# TestMod_SEAx.net
KiCad netlist of a schematic drawn in Altium Designer
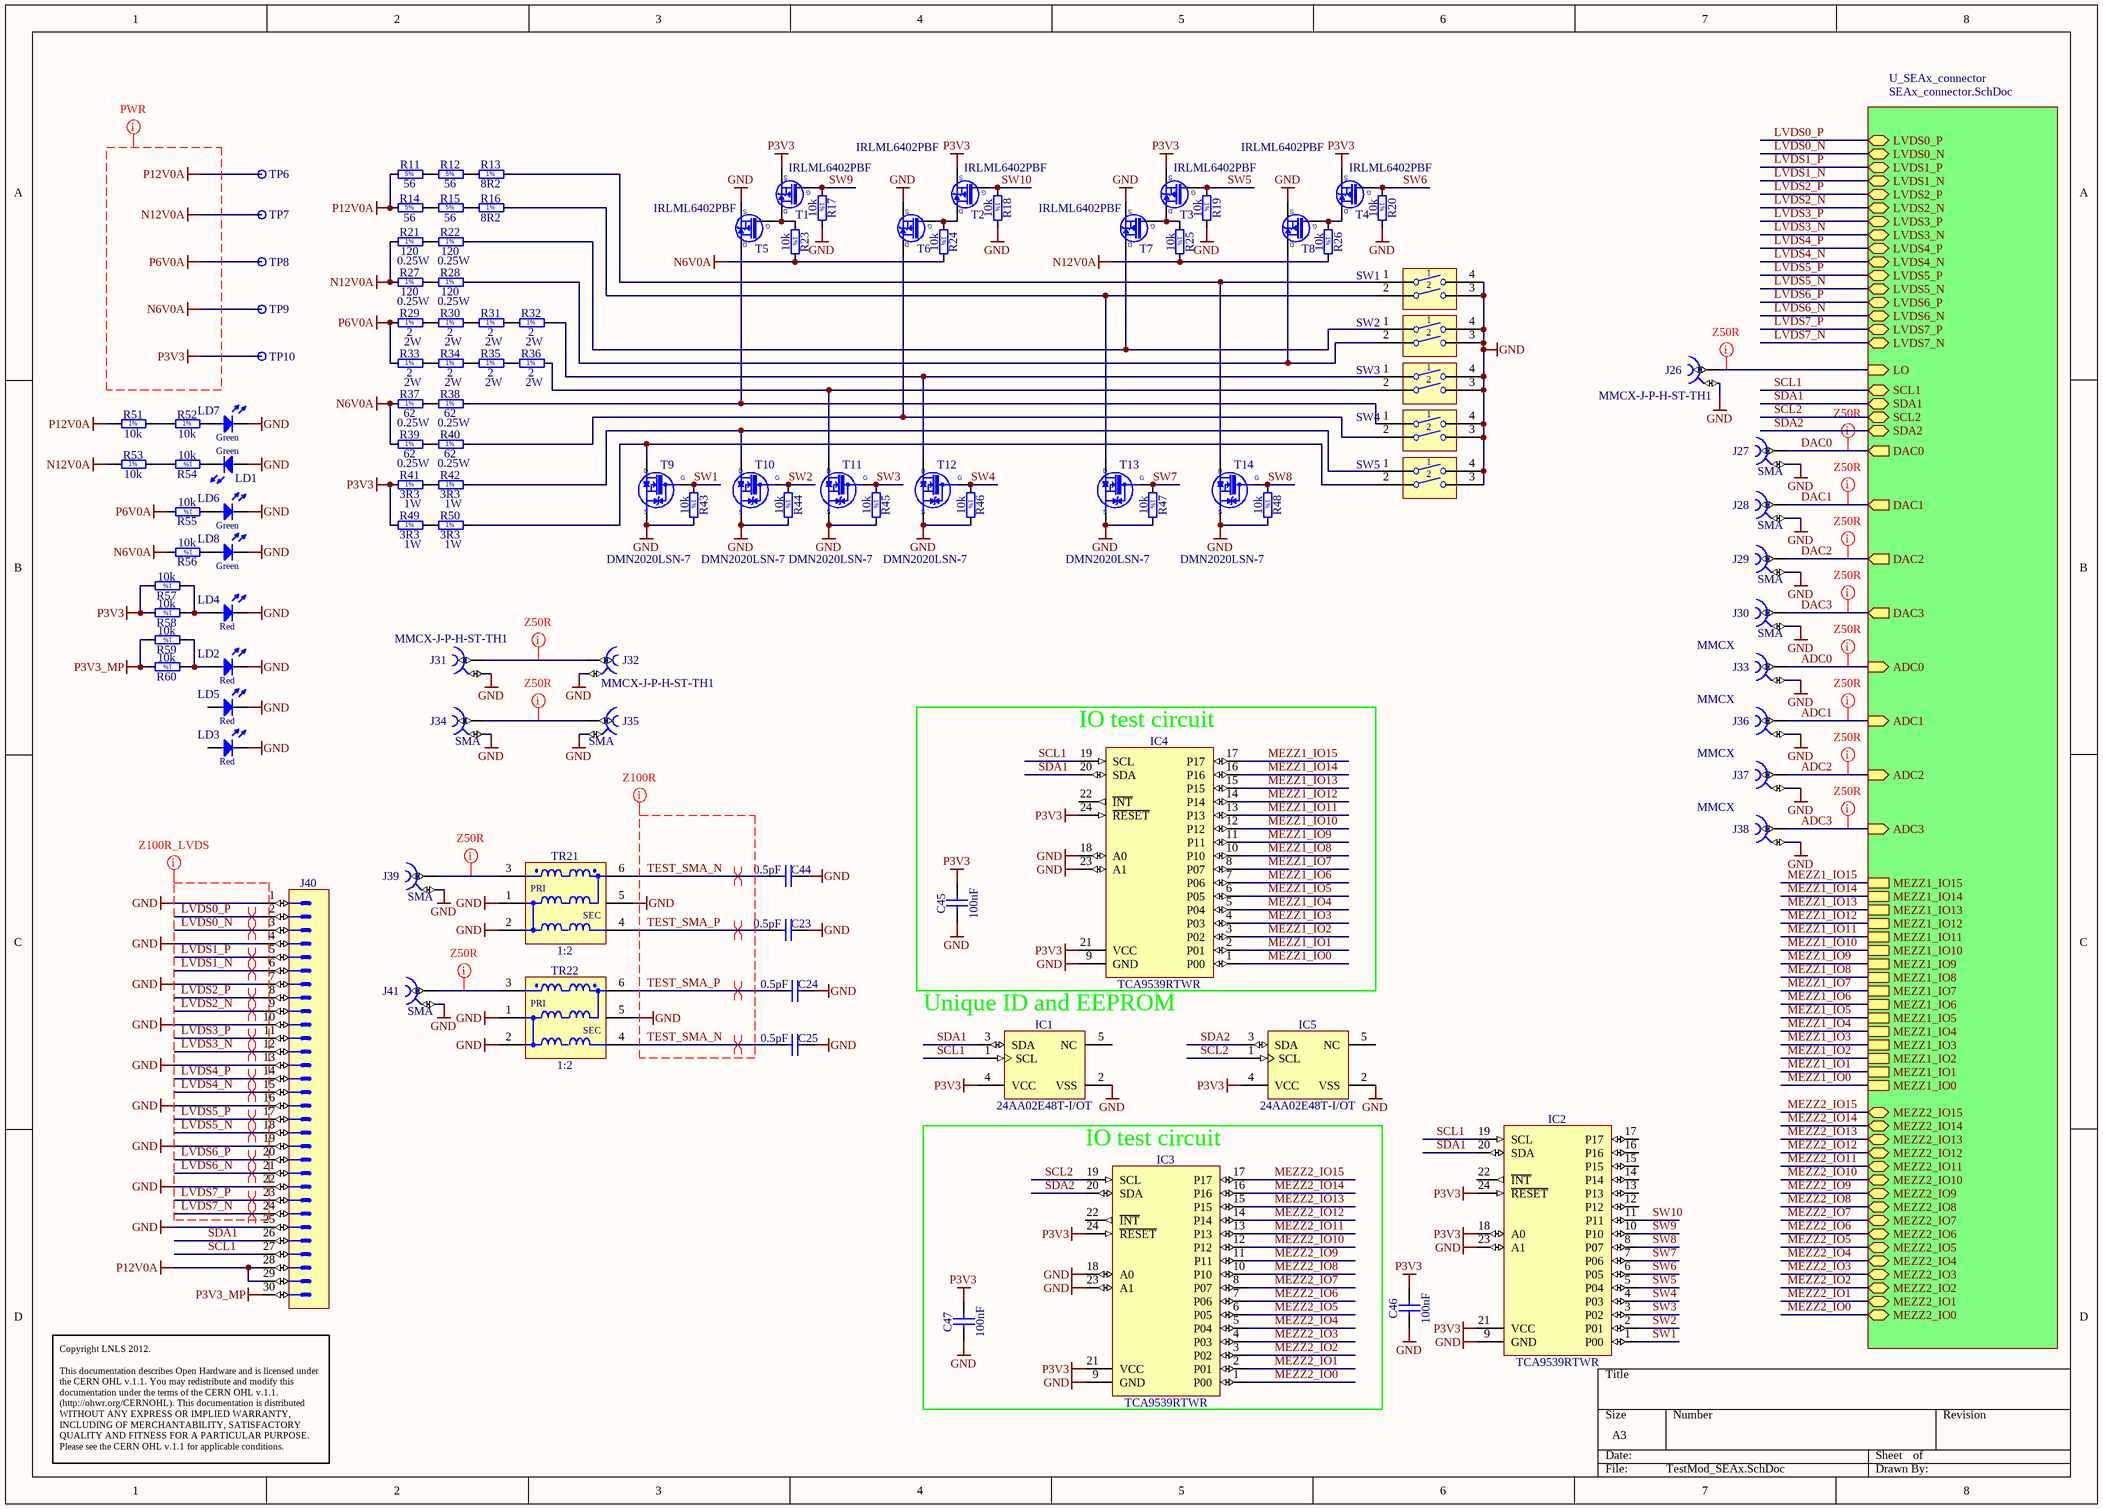
[diagram p0: TestMod_SEAx.SchDoc]

(export (version "E")
  (design (tool "Eeschema 10.0.6"))
  (components
    (comp (ref "C23")
      (value "0.5pF")
      (footprint "CAPC1005X50N")
      (description "Non-polarised capacitor")
      (fields
        (field (name "PART NUMBER") "CC0402_0.5PF_25V_0.05PF_AVX_04023J0R5ABSTR")
        (field (name "VOLTAGE") "25V")
        (field (name "AUTHOR") "CERN DEM JLC")
      )
      (libsource (lib "Capacitors") (part "Capacitor - non polarized"))
    )
    (comp (ref "C24")
      (value "0.5pF")
      (footprint "CAPC1005X50N")
      (description "Non-polarised capacitor")
      (fields
        (field (name "PART NUMBER") "CC0402_0.5PF_25V_0.05PF_AVX_04023J0R5ABSTR")
        (field (name "VOLTAGE") "25V")
        (field (name "AUTHOR") "CERN DEM JLC")
      )
      (libsource (lib "Capacitors") (part "Capacitor - non polarized"))
    )
    (comp (ref "C25")
      (value "0.5pF")
      (footprint "CAPC1005X50N")
      (description "Non-polarised capacitor")
      (fields
        (field (name "PART NUMBER") "CC0402_0.5PF_25V_0.05PF_AVX_04023J0R5ABSTR")
        (field (name "VOLTAGE") "25V")
        (field (name "AUTHOR") "CERN DEM JLC")
      )
      (libsource (lib "Capacitors") (part "Capacitor - non polarized"))
    )
    (comp (ref "C44")
      (value "0.5pF")
      (footprint "CAPC1005X50N")
      (description "Non-polarised capacitor")
      (fields
        (field (name "PART NUMBER") "CC0402_0.5PF_25V_0.05PF_AVX_04023J0R5ABSTR")
        (field (name "VOLTAGE") "25V")
        (field (name "AUTHOR") "CERN DEM JLC")
      )
      (libsource (lib "Capacitors") (part "Capacitor - non polarized"))
    )
    (comp (ref "C45")
      (value "100nF")
      (footprint "CAPC1005X55N")
      (description "Non-polarised capacitor")
      (fields
        (field (name "PART NUMBER") "CC0402_100NF_16V_10%_X5R")
        (field (name "VOLTAGE") "16V")
        (field (name "AUTHOR") "CERN DEM JLC")
      )
      (libsource (lib "Capacitors") (part "Capacitor - non polarized"))
    )
    (comp (ref "C46")
      (value "100nF")
      (footprint "CAPC1005X55N")
      (description "Non-polarised capacitor")
      (fields
        (field (name "PART NUMBER") "CC0402_100NF_16V_10%_X5R")
        (field (name "VOLTAGE") "16V")
        (field (name "AUTHOR") "CERN DEM JLC")
      )
      (libsource (lib "Capacitors") (part "Capacitor - non polarized"))
    )
    (comp (ref "C47")
      (value "100nF")
      (footprint "CAPC1005X55N")
      (description "Non-polarised capacitor")
      (fields
        (field (name "PART NUMBER") "CC0402_100NF_16V_10%_X5R")
        (field (name "VOLTAGE") "16V")
        (field (name "AUTHOR") "CERN DEM JLC")
      )
      (libsource (lib "Capacitors") (part "Capacitor - non polarized"))
    )
    (comp (ref "IC1")
      (value "24AA02E48T-I/OT")
      (footprint "SOT95P280X145-5N")
      (description "1.7V-5.5V, 2K I2C Serial EEPROM With EUI-48 Node Identity")
      (fields (field (name "MANUFACTURER") "MICROCHIP TECHNOLOGY") (field (name "AUTHOR") "CERN DEM MR"))
      (libsource (lib "ICs And Semiconductors") (part "24AA02E48T-I/OT"))
    )
    (comp (ref "IC2")
      (value "TCA9539RTWR")
      (footprint "QFN50P400X400X80-25N-S255")
      (description "Low-Voltage 16-Bit I2C and SMBus I/O Expander")
      (fields (field (name "MANUFACTURER") "TEXAS INSTRUMENTS") (field (name "AUTHOR") "CERN DEM MR"))
      (libsource (lib "ICs And Semiconductors") (part "TCA9539RTWR"))
    )
    (comp (ref "IC3")
      (value "TCA9539RTWR")
      (footprint "QFN50P400X400X80-25N-S255")
      (description "Low-Voltage 16-Bit I2C and SMBus I/O Expander")
      (fields (field (name "MANUFACTURER") "TEXAS INSTRUMENTS") (field (name "AUTHOR") "CERN DEM MR"))
      (libsource (lib "ICs And Semiconductors") (part "TCA9539RTWR"))
    )
    (comp (ref "IC4")
      (value "TCA9539RTWR")
      (footprint "QFN50P400X400X80-25N-S255")
      (description "Low-Voltage 16-Bit I2C and SMBus I/O Expander")
      (fields (field (name "MANUFACTURER") "TEXAS INSTRUMENTS") (field (name "AUTHOR") "CERN DEM MR"))
      (libsource (lib "ICs And Semiconductors") (part "TCA9539RTWR"))
    )
    (comp (ref "IC5")
      (value "24AA02E48T-I/OT")
      (footprint "SOT95P280X145-5N")
      (description "1.7V-5.5V, 2K I2C Serial EEPROM With EUI-48 Node Identity")
      (fields (field (name "MANUFACTURER") "MICROCHIP TECHNOLOGY") (field (name "AUTHOR") "CERN DEM MR"))
      (libsource (lib "ICs And Semiconductors") (part "24AA02E48T-I/OT"))
    )
    (comp (ref "J26")
      (value "Coax_1Female_1Shield")
      (footprint "SAMTEC_MMCX-J-P-H-ST-TH1")
      (fields
        (field (name "PART NUMBER") "SAMTEC_MMCX-J-P-H-ST-TH1")
        (field (name "MANUFACTURER") "SAMTEC")
        (field (name "MANUFACTURER PART NUMBER") "MMCX-J-P-H-ST-TH1")
        (field (name "AUTHOR") "CERN DEM JLC")
      )
      (libsource (lib "Connectors") (part "Coax_1Female_1Shield"))
    )
    (comp (ref "J27")
      (value "SMA")
      (footprint "AMPHENOL_901-143_IN BOARD")
      (description "AMPHENOL_901-143")
      (fields
        (field (name "MANUFACTURER") "AMPHENOL")
        (field (name "MANUFACTURER PART NUMBER") "901-143")
        (field (name "AUTHOR") "LNLS DIG GBMB")
      )
      (libsource (lib "LIBRARY_SCH") (part "CON_SMA_RA_AMP"))
    )
    (comp (ref "J28")
      (value "SMA")
      (footprint "AMPHENOL_901-143_IN BOARD")
      (description "AMPHENOL_901-143")
      (fields
        (field (name "MANUFACTURER") "AMPHENOL")
        (field (name "MANUFACTURER PART NUMBER") "901-143")
        (field (name "AUTHOR") "LNLS DIG GBMB")
      )
      (libsource (lib "LIBRARY_SCH") (part "CON_SMA_RA_AMP"))
    )
    (comp (ref "J29")
      (value "SMA")
      (footprint "AMPHENOL_901-143_IN BOARD")
      (description "AMPHENOL_901-143")
      (fields
        (field (name "MANUFACTURER") "AMPHENOL")
        (field (name "MANUFACTURER PART NUMBER") "901-143")
        (field (name "AUTHOR") "LNLS DIG GBMB")
      )
      (libsource (lib "LIBRARY_SCH") (part "CON_SMA_RA_AMP"))
    )
    (comp (ref "J30")
      (value "SMA")
      (footprint "AMPHENOL_901-143_IN BOARD")
      (description "AMPHENOL_901-143")
      (fields
        (field (name "MANUFACTURER") "AMPHENOL")
        (field (name "MANUFACTURER PART NUMBER") "901-143")
        (field (name "AUTHOR") "LNLS DIG GBMB")
      )
      (libsource (lib "LIBRARY_SCH") (part "CON_SMA_RA_AMP"))
    )
    (comp (ref "J31")
      (value "Coax_1Female_1Shield")
      (footprint "SAMTEC_MMCX-J-P-H-ST-TH1")
      (fields
        (field (name "PART NUMBER") "SAMTEC_MMCX-J-P-H-ST-TH1")
        (field (name "MANUFACTURER") "SAMTEC")
        (field (name "MANUFACTURER PART NUMBER") "MMCX-J-P-H-ST-TH1")
        (field (name "AUTHOR") "CERN DEM JLC")
      )
      (libsource (lib "Connectors") (part "Coax_1Female_1Shield"))
    )
    (comp (ref "J32")
      (value "Coax_1Female_1Shield")
      (footprint "SAMTEC_MMCX-J-P-H-ST-TH1")
      (fields
        (field (name "PART NUMBER") "SAMTEC_MMCX-J-P-H-ST-TH1")
        (field (name "MANUFACTURER") "SAMTEC")
        (field (name "MANUFACTURER PART NUMBER") "MMCX-J-P-H-ST-TH1")
        (field (name "AUTHOR") "CERN DEM JLC")
      )
      (libsource (lib "") (part "Coax_1Female_1Shield_1"))
    )
    (comp (ref "J33")
      (value "Coax_1Female_1Shield")
      (footprint "HUBER-SUHNER_85_MMCX-50-0-1/111_OE")
      (fields
        (field (name "PART NUMBER") "HUBER-SUHNER_85_MMCX-50-0-1/111_OE")
        (field (name "FAMILY") "MMCX")
        (field (name "MANUFACTURER") "HUBER+SUHNER")
        (field (name "MANUFACTURER PART NUMBER") "85_MMCX-50-0-1/111_OE")
        (field (name "AUTHOR") "CERN DEM JLC")
      )
      (libsource (lib "Connectors") (part "Coax_1Female_1Shield"))
    )
    (comp (ref "J34")
      (value "SMA")
      (footprint "TYCO_5-1814832-1")
      (fields
        (field (name "PART NUMBER") "TYCO_5-1814832-1")
        (field (name "MANUFACTURER") "TYCO ELECTRONICS")
        (field (name "MANUFACTURER PART NUMBER") "5-1814832-1")
        (field (name "AUTHOR") "CERN DEM JLC")
      )
      (libsource (lib "Connectors") (part "Coax_1Female_1Shield"))
    )
    (comp (ref "J35")
      (value "SMA")
      (footprint "TYCO_5-1814832-1")
      (fields
        (field (name "PART NUMBER") "TYCO_5-1814832-1")
        (field (name "MANUFACTURER") "TYCO ELECTRONICS")
        (field (name "MANUFACTURER PART NUMBER") "5-1814832-1")
        (field (name "AUTHOR") "CERN DEM JLC")
      )
      (libsource (lib "") (part "Coax_1Female_1Shield_1"))
    )
    (comp (ref "J36")
      (value "Coax_1Female_1Shield")
      (footprint "HUBER-SUHNER_85_MMCX-50-0-1/111_OE")
      (fields
        (field (name "PART NUMBER") "HUBER-SUHNER_85_MMCX-50-0-1/111_OE")
        (field (name "FAMILY") "MMCX")
        (field (name "MANUFACTURER") "HUBER+SUHNER")
        (field (name "MANUFACTURER PART NUMBER") "85_MMCX-50-0-1/111_OE")
        (field (name "AUTHOR") "CERN DEM JLC")
      )
      (libsource (lib "Connectors") (part "Coax_1Female_1Shield"))
    )
    (comp (ref "J37")
      (value "Coax_1Female_1Shield")
      (footprint "HUBER-SUHNER_85_MMCX-50-0-1/111_OE")
      (fields
        (field (name "PART NUMBER") "HUBER-SUHNER_85_MMCX-50-0-1/111_OE")
        (field (name "FAMILY") "MMCX")
        (field (name "MANUFACTURER") "HUBER+SUHNER")
        (field (name "MANUFACTURER PART NUMBER") "85_MMCX-50-0-1/111_OE")
        (field (name "AUTHOR") "CERN DEM JLC")
      )
      (libsource (lib "Connectors") (part "Coax_1Female_1Shield"))
    )
    (comp (ref "J38")
      (value "Coax_1Female_1Shield")
      (footprint "HUBER-SUHNER_85_MMCX-50-0-1/111_OE")
      (fields
        (field (name "PART NUMBER") "HUBER-SUHNER_85_MMCX-50-0-1/111_OE")
        (field (name "FAMILY") "MMCX")
        (field (name "MANUFACTURER") "HUBER+SUHNER")
        (field (name "MANUFACTURER PART NUMBER") "85_MMCX-50-0-1/111_OE")
        (field (name "AUTHOR") "CERN DEM JLC")
      )
      (libsource (lib "Connectors") (part "Coax_1Female_1Shield"))
    )
    (comp (ref "J39")
      (value "SMA")
      (footprint "TYCO_5-1814832-1")
      (fields
        (field (name "PART NUMBER") "TYCO_5-1814832-1")
        (field (name "MANUFACTURER") "TYCO ELECTRONICS")
        (field (name "MANUFACTURER PART NUMBER") "5-1814832-1")
        (field (name "AUTHOR") "CERN DEM JLC")
      )
      (libsource (lib "Connectors") (part "Coax_1Female_1Shield"))
    )
    (comp (ref "J40")
      (value "~")
      (footprint "3M_N2530-6002RB")
      (description "Connector 30 Male")
      (fields
        (field (name "PART NUMBER") "3M_N2530-6002RB")
        (field (name "MANUFACTURER") "3M")
        (field (name "AUTHOR") "CERN DEM JLC")
      )
      (libsource (lib "Connectors") (part "Connector 30 Male"))
    )
    (comp (ref "J41")
      (value "SMA")
      (footprint "TYCO_5-1814832-1")
      (fields
        (field (name "PART NUMBER") "TYCO_5-1814832-1")
        (field (name "MANUFACTURER") "TYCO ELECTRONICS")
        (field (name "MANUFACTURER PART NUMBER") "5-1814832-1")
        (field (name "AUTHOR") "CERN DEM JLC")
      )
      (libsource (lib "Connectors") (part "Coax_1Female_1Shield"))
    )
    (comp (ref "LD1")
      (value "Green")
      (footprint "LED_KINGBRIGHT_L-13GD")
      (description "LED Green 2mm")
      (fields
        (field (name "PART NUMBER") "LED_KINGBRIGHT_L-13GD")
        (field (name "MANUFACTURER") "KINGBRIGHT")
        (field (name "AUTHOR") "GK")
      )
      (libsource (lib "LIBRARY_SCH") (part "LED_2mm_RA_Green"))
    )
    (comp (ref "LD2")
      (value "Red")
      (footprint "LED_KINGBRIGHT_L-13ID")
      (description "LED Red 2mm")
      (fields
        (field (name "PART NUMBER") "LED_KINGBRIGHT_L-13ID")
        (field (name "MANUFACTURER") "KINGBRIGHT")
        (field (name "AUTHOR") "GK")
      )
      (libsource (lib "LIBRARY_SCH") (part "LED_2mm_RA_Red"))
    )
    (comp (ref "LD3")
      (value "Red")
      (footprint "LED_KINGBRIGHT_L-13ID")
      (description "LED Red 2mm")
      (fields
        (field (name "PART NUMBER") "LED_KINGBRIGHT_L-13ID")
        (field (name "MANUFACTURER") "KINGBRIGHT")
        (field (name "AUTHOR") "GK")
      )
      (libsource (lib "LIBRARY_SCH") (part "LED_2mm_RA_Red"))
    )
    (comp (ref "LD4")
      (value "Red")
      (footprint "LED_KINGBRIGHT_L-13ID")
      (description "LED Red 2mm")
      (fields
        (field (name "PART NUMBER") "LED_KINGBRIGHT_L-13ID")
        (field (name "MANUFACTURER") "KINGBRIGHT")
        (field (name "AUTHOR") "GK")
      )
      (libsource (lib "LIBRARY_SCH") (part "LED_2mm_RA_Red"))
    )
    (comp (ref "LD5")
      (value "Red")
      (footprint "LED_KINGBRIGHT_L-13ID")
      (description "LED Red 2mm")
      (fields
        (field (name "PART NUMBER") "LED_KINGBRIGHT_L-13ID")
        (field (name "MANUFACTURER") "KINGBRIGHT")
        (field (name "AUTHOR") "GK")
      )
      (libsource (lib "LIBRARY_SCH") (part "LED_2mm_RA_Red"))
    )
    (comp (ref "LD6")
      (value "Green")
      (footprint "LED_KINGBRIGHT_L-13GD")
      (description "LED Green 2mm")
      (fields
        (field (name "PART NUMBER") "LED_KINGBRIGHT_L-13GD")
        (field (name "MANUFACTURER") "KINGBRIGHT")
        (field (name "AUTHOR") "GK")
      )
      (libsource (lib "LIBRARY_SCH") (part "LED_2mm_RA_Green"))
    )
    (comp (ref "LD7")
      (value "Green")
      (footprint "LED_KINGBRIGHT_L-13GD")
      (description "LED Green 2mm")
      (fields
        (field (name "PART NUMBER") "LED_KINGBRIGHT_L-13GD")
        (field (name "MANUFACTURER") "KINGBRIGHT")
        (field (name "AUTHOR") "GK")
      )
      (libsource (lib "LIBRARY_SCH") (part "LED_2mm_RA_Green"))
    )
    (comp (ref "LD8")
      (value "Green")
      (footprint "LED_KINGBRIGHT_L-13GD")
      (description "LED Green 2mm")
      (fields
        (field (name "PART NUMBER") "LED_KINGBRIGHT_L-13GD")
        (field (name "MANUFACTURER") "KINGBRIGHT")
        (field (name "AUTHOR") "GK")
      )
      (libsource (lib "LIBRARY_SCH") (part "LED_2mm_RA_Green"))
    )
    (comp (ref "R11")
      (value "56")
      (footprint "RESC6331X70N")
      (description "Resistor - 5%")
      (fields
        (field (name "PART NUMBER") "R2512_56R_5%_1W_200PPM")
        (field (name "POWER") "1W")
        (field (name "AUTHOR") "CERN DEM JLC")
      )
      (libsource (lib "Resistors") (part "Resistor - 5%"))
    )
    (comp (ref "R12")
      (value "56")
      (footprint "RESC6331X70N")
      (description "Resistor - 5%")
      (fields
        (field (name "PART NUMBER") "R2512_56R_5%_1W_200PPM")
        (field (name "POWER") "1W")
        (field (name "AUTHOR") "CERN DEM JLC")
      )
      (libsource (lib "Resistors") (part "Resistor - 5%"))
    )
    (comp (ref "R13")
      (value "8R2")
      (footprint "RESC3216X65N")
      (description "Resistor - 1%")
      (fields
        (field (name "PART NUMBER") "R1206_8R2_1%_0.25W_200PPM")
        (field (name "POWER") "0.25W")
        (field (name "AUTHOR") "CERN DEM JLC")
      )
      (libsource (lib "Resistors") (part "Resistor - 1%"))
    )
    (comp (ref "R14")
      (value "56")
      (footprint "RESC6331X70N")
      (description "Resistor - 5%")
      (fields
        (field (name "PART NUMBER") "R2512_56R_5%_1W_200PPM")
        (field (name "POWER") "1W")
        (field (name "AUTHOR") "CERN DEM JLC")
      )
      (libsource (lib "Resistors") (part "Resistor - 5%"))
    )
    (comp (ref "R15")
      (value "56")
      (footprint "RESC6331X70N")
      (description "Resistor - 5%")
      (fields
        (field (name "PART NUMBER") "R2512_56R_5%_1W_200PPM")
        (field (name "POWER") "1W")
        (field (name "AUTHOR") "CERN DEM JLC")
      )
      (libsource (lib "Resistors") (part "Resistor - 5%"))
    )
    (comp (ref "R16")
      (value "8R2")
      (footprint "RESC3216X65N")
      (description "Resistor - 1%")
      (fields
        (field (name "PART NUMBER") "R1206_8R2_1%_0.25W_200PPM")
        (field (name "POWER") "0.25W")
        (field (name "AUTHOR") "CERN DEM JLC")
      )
      (libsource (lib "Resistors") (part "Resistor - 1%"))
    )
    (comp (ref "R17")
      (value "10k")
      (footprint "RESC1005X40N")
      (description "Resistor - 1%")
      (fields
        (field (name "PART NUMBER") "R0402_10K_1%_0.0625W_100PPM")
        (field (name "POWER") "0.0625W")
        (field (name "AUTHOR") "CERN DEM JLC")
      )
      (libsource (lib "Resistors") (part "Resistor - 1%"))
    )
    (comp (ref "R18")
      (value "10k")
      (footprint "RESC1005X40N")
      (description "Resistor - 1%")
      (fields
        (field (name "PART NUMBER") "R0402_10K_1%_0.0625W_100PPM")
        (field (name "POWER") "0.0625W")
        (field (name "AUTHOR") "CERN DEM JLC")
      )
      (libsource (lib "Resistors") (part "Resistor - 1%"))
    )
    (comp (ref "R19")
      (value "10k")
      (footprint "RESC1005X40N")
      (description "Resistor - 1%")
      (fields
        (field (name "PART NUMBER") "R0402_10K_1%_0.0625W_100PPM")
        (field (name "POWER") "0.0625W")
        (field (name "AUTHOR") "CERN DEM JLC")
      )
      (libsource (lib "Resistors") (part "Resistor - 1%"))
    )
    (comp (ref "R20")
      (value "10k")
      (footprint "RESC1005X40N")
      (description "Resistor - 1%")
      (fields
        (field (name "PART NUMBER") "R0402_10K_1%_0.0625W_100PPM")
        (field (name "POWER") "0.0625W")
        (field (name "AUTHOR") "CERN DEM JLC")
      )
      (libsource (lib "Resistors") (part "Resistor - 1%"))
    )
    (comp (ref "R21")
      (value "120")
      (footprint "RESC3216X65N")
      (description "Resistor - 1%")
      (fields
        (field (name "PART NUMBER") "R1206_120R_1%_0.25W_100PPM")
        (field (name "POWER") "0.25W")
        (field (name "TOLERANCE") "±1%")
        (field (name "AUTHOR") "CERN DEM JLC")
      )
      (libsource (lib "Resistors") (part "Resistor - 1%"))
    )
    (comp (ref "R22")
      (value "120")
      (footprint "RESC3216X65N")
      (description "Resistor - 1%")
      (fields
        (field (name "PART NUMBER") "R1206_120R_1%_0.25W_100PPM")
        (field (name "POWER") "0.25W")
        (field (name "TOLERANCE") "±1%")
        (field (name "AUTHOR") "CERN DEM JLC")
      )
      (libsource (lib "Resistors") (part "Resistor - 1%"))
    )
    (comp (ref "R23")
      (value "10k")
      (footprint "RESC1005X40N")
      (description "Resistor - 1%")
      (fields
        (field (name "PART NUMBER") "R0402_10K_1%_0.0625W_100PPM")
        (field (name "POWER") "0.0625W")
        (field (name "AUTHOR") "CERN DEM JLC")
      )
      (libsource (lib "Resistors") (part "Resistor - 1%"))
    )
    (comp (ref "R24")
      (value "10k")
      (footprint "RESC1005X40N")
      (description "Resistor - 1%")
      (fields
        (field (name "PART NUMBER") "R0402_10K_1%_0.0625W_100PPM")
        (field (name "POWER") "0.0625W")
        (field (name "AUTHOR") "CERN DEM JLC")
      )
      (libsource (lib "Resistors") (part "Resistor - 1%"))
    )
    (comp (ref "R25")
      (value "10k")
      (footprint "RESC1005X40N")
      (description "Resistor - 1%")
      (fields
        (field (name "PART NUMBER") "R0402_10K_1%_0.0625W_100PPM")
        (field (name "POWER") "0.0625W")
        (field (name "AUTHOR") "CERN DEM JLC")
      )
      (libsource (lib "Resistors") (part "Resistor - 1%"))
    )
    (comp (ref "R26")
      (value "10k")
      (footprint "RESC1005X40N")
      (description "Resistor - 1%")
      (fields
        (field (name "PART NUMBER") "R0402_10K_1%_0.0625W_100PPM")
        (field (name "POWER") "0.0625W")
        (field (name "AUTHOR") "CERN DEM JLC")
      )
      (libsource (lib "Resistors") (part "Resistor - 1%"))
    )
    (comp (ref "R27")
      (value "120")
      (footprint "RESC3216X65N")
      (description "Resistor - 1%")
      (fields
        (field (name "PART NUMBER") "R1206_120R_1%_0.25W_100PPM")
        (field (name "POWER") "0.25W")
        (field (name "TOLERANCE") "±1%")
        (field (name "AUTHOR") "CERN DEM JLC")
      )
      (libsource (lib "Resistors") (part "Resistor - 1%"))
    )
    (comp (ref "R28")
      (value "120")
      (footprint "RESC3216X65N")
      (description "Resistor - 1%")
      (fields
        (field (name "PART NUMBER") "R1206_120R_1%_0.25W_100PPM")
        (field (name "POWER") "0.25W")
        (field (name "TOLERANCE") "±1%")
        (field (name "AUTHOR") "CERN DEM JLC")
      )
      (libsource (lib "Resistors") (part "Resistor - 1%"))
    )
    (comp (ref "R29")
      (value "2")
      (footprint "RESM11670X449N")
      (description "Resistor - 1%")
      (fields
        (field (name "PART NUMBER") "R4527_2R_1%_2W_50PPM")
        (field (name "POWER") "2W")
        (field (name "TOLERANCE") "±1%")
        (field (name "AUTHOR") "CERN DEM JLC")
      )
      (libsource (lib "Resistors") (part "Resistor - 1%"))
    )
    (comp (ref "R30")
      (value "2")
      (footprint "RESM11670X449N")
      (description "Resistor - 1%")
      (fields
        (field (name "PART NUMBER") "R4527_2R_1%_2W_50PPM")
        (field (name "POWER") "2W")
        (field (name "TOLERANCE") "±1%")
        (field (name "AUTHOR") "CERN DEM JLC")
      )
      (libsource (lib "Resistors") (part "Resistor - 1%"))
    )
    (comp (ref "R31")
      (value "2")
      (footprint "RESM11670X449N")
      (description "Resistor - 1%")
      (fields
        (field (name "PART NUMBER") "R4527_2R_1%_2W_50PPM")
        (field (name "POWER") "2W")
        (field (name "TOLERANCE") "±1%")
        (field (name "AUTHOR") "CERN DEM JLC")
      )
      (libsource (lib "Resistors") (part "Resistor - 1%"))
    )
    (comp (ref "R32")
      (value "2")
      (footprint "RESM11670X449N")
      (description "Resistor - 1%")
      (fields
        (field (name "PART NUMBER") "R4527_2R_1%_2W_50PPM")
        (field (name "POWER") "2W")
        (field (name "TOLERANCE") "±1%")
        (field (name "AUTHOR") "CERN DEM JLC")
      )
      (libsource (lib "Resistors") (part "Resistor - 1%"))
    )
    (comp (ref "R33")
      (value "2")
      (footprint "RESM11670X449N")
      (description "Resistor - 1%")
      (fields
        (field (name "PART NUMBER") "R4527_2R_1%_2W_50PPM")
        (field (name "POWER") "2W")
        (field (name "TOLERANCE") "±1%")
        (field (name "AUTHOR") "CERN DEM JLC")
      )
      (libsource (lib "Resistors") (part "Resistor - 1%"))
    )
    (comp (ref "R34")
      (value "2")
      (footprint "RESM11670X449N")
      (description "Resistor - 1%")
      (fields
        (field (name "PART NUMBER") "R4527_2R_1%_2W_50PPM")
        (field (name "POWER") "2W")
        (field (name "TOLERANCE") "±1%")
        (field (name "AUTHOR") "CERN DEM JLC")
      )
      (libsource (lib "Resistors") (part "Resistor - 1%"))
    )
    (comp (ref "R35")
      (value "2")
      (footprint "RESM11670X449N")
      (description "Resistor - 1%")
      (fields
        (field (name "PART NUMBER") "R4527_2R_1%_2W_50PPM")
        (field (name "POWER") "2W")
        (field (name "TOLERANCE") "±1%")
        (field (name "AUTHOR") "CERN DEM JLC")
      )
      (libsource (lib "Resistors") (part "Resistor - 1%"))
    )
    (comp (ref "R36")
      (value "2")
      (footprint "RESM11670X449N")
      (description "Resistor - 1%")
      (fields
        (field (name "PART NUMBER") "R4527_2R_1%_2W_50PPM")
        (field (name "POWER") "2W")
        (field (name "TOLERANCE") "±1%")
        (field (name "AUTHOR") "CERN DEM JLC")
      )
      (libsource (lib "Resistors") (part "Resistor - 1%"))
    )
    (comp (ref "R37")
      (value "62")
      (footprint "RESC3216X65N")
      (description "Resistor - 1%")
      (fields
        (field (name "PART NUMBER") "R1206_62R_1%_0.25W_100PPM")
        (field (name "POWER") "0.25W")
        (field (name "TOLERANCE") "±1%")
        (field (name "AUTHOR") "CERN DEM JLC")
      )
      (libsource (lib "Resistors") (part "Resistor - 1%"))
    )
    (comp (ref "R38")
      (value "62")
      (footprint "RESC3216X65N")
      (description "Resistor - 1%")
      (fields
        (field (name "PART NUMBER") "R1206_62R_1%_0.25W_100PPM")
        (field (name "POWER") "0.25W")
        (field (name "TOLERANCE") "±1%")
        (field (name "AUTHOR") "CERN DEM JLC")
      )
      (libsource (lib "Resistors") (part "Resistor - 1%"))
    )
    (comp (ref "R39")
      (value "62")
      (footprint "RESC3216X65N")
      (description "Resistor - 1%")
      (fields
        (field (name "PART NUMBER") "R1206_62R_1%_0.25W_100PPM")
        (field (name "POWER") "0.25W")
        (field (name "TOLERANCE") "±1%")
        (field (name "AUTHOR") "CERN DEM JLC")
      )
      (libsource (lib "Resistors") (part "Resistor - 1%"))
    )
    (comp (ref "R40")
      (value "62")
      (footprint "RESC3216X65N")
      (description "Resistor - 1%")
      (fields
        (field (name "PART NUMBER") "R1206_62R_1%_0.25W_100PPM")
        (field (name "POWER") "0.25W")
        (field (name "TOLERANCE") "±1%")
        (field (name "AUTHOR") "CERN DEM JLC")
      )
      (libsource (lib "Resistors") (part "Resistor - 1%"))
    )
    (comp (ref "R41")
      (value "3R3")
      (footprint "RESC6331X70N")
      (description "Resistor - 1%")
      (fields
        (field (name "PART NUMBER") "R2512_3R3_1%_1W_200PPM")
        (field (name "POWER") "1W")
        (field (name "TOLERANCE") "±1%")
        (field (name "AUTHOR") "CERN DEM JLC")
      )
      (libsource (lib "Resistors") (part "Resistor - 1%"))
    )
    (comp (ref "R42")
      (value "3R3")
      (footprint "RESC6331X70N")
      (description "Resistor - 1%")
      (fields
        (field (name "PART NUMBER") "R2512_3R3_1%_1W_200PPM")
        (field (name "POWER") "1W")
        (field (name "TOLERANCE") "±1%")
        (field (name "AUTHOR") "CERN DEM JLC")
      )
      (libsource (lib "Resistors") (part "Resistor - 1%"))
    )
    (comp (ref "R43")
      (value "10k")
      (footprint "RESC1005X40N")
      (description "Resistor - 1%")
      (fields
        (field (name "PART NUMBER") "R0402_10K_1%_0.0625W_100PPM")
        (field (name "POWER") "0.0625W")
        (field (name "AUTHOR") "CERN DEM JLC")
      )
      (libsource (lib "Resistors") (part "Resistor - 1%"))
    )
    (comp (ref "R44")
      (value "10k")
      (footprint "RESC1005X40N")
      (description "Resistor - 1%")
      (fields
        (field (name "PART NUMBER") "R0402_10K_1%_0.0625W_100PPM")
        (field (name "POWER") "0.0625W")
        (field (name "AUTHOR") "CERN DEM JLC")
      )
      (libsource (lib "Resistors") (part "Resistor - 1%"))
    )
    (comp (ref "R45")
      (value "10k")
      (footprint "RESC1005X40N")
      (description "Resistor - 1%")
      (fields
        (field (name "PART NUMBER") "R0402_10K_1%_0.0625W_100PPM")
        (field (name "POWER") "0.0625W")
        (field (name "AUTHOR") "CERN DEM JLC")
      )
      (libsource (lib "Resistors") (part "Resistor - 1%"))
    )
    (comp (ref "R46")
      (value "10k")
      (footprint "RESC1005X40N")
      (description "Resistor - 1%")
      (fields
        (field (name "PART NUMBER") "R0402_10K_1%_0.0625W_100PPM")
        (field (name "POWER") "0.0625W")
        (field (name "AUTHOR") "CERN DEM JLC")
      )
      (libsource (lib "Resistors") (part "Resistor - 1%"))
    )
    (comp (ref "R47")
      (value "10k")
      (footprint "RESC1005X40N")
      (description "Resistor - 1%")
      (fields
        (field (name "PART NUMBER") "R0402_10K_1%_0.0625W_100PPM")
        (field (name "POWER") "0.0625W")
        (field (name "AUTHOR") "CERN DEM JLC")
      )
      (libsource (lib "Resistors") (part "Resistor - 1%"))
    )
    (comp (ref "R48")
      (value "10k")
      (footprint "RESC1005X40N")
      (description "Resistor - 1%")
      (fields
        (field (name "PART NUMBER") "R0402_10K_1%_0.0625W_100PPM")
        (field (name "POWER") "0.0625W")
        (field (name "AUTHOR") "CERN DEM JLC")
      )
      (libsource (lib "Resistors") (part "Resistor - 1%"))
    )
    (comp (ref "R49")
      (value "3R3")
      (footprint "RESC6331X70N")
      (description "Resistor - 1%")
      (fields
        (field (name "PART NUMBER") "R2512_3R3_1%_1W_200PPM")
        (field (name "POWER") "1W")
        (field (name "TOLERANCE") "±1%")
        (field (name "AUTHOR") "CERN DEM JLC")
      )
      (libsource (lib "Resistors") (part "Resistor - 1%"))
    )
    (comp (ref "R50")
      (value "3R3")
      (footprint "RESC6331X70N")
      (description "Resistor - 1%")
      (fields
        (field (name "PART NUMBER") "R2512_3R3_1%_1W_200PPM")
        (field (name "POWER") "1W")
        (field (name "TOLERANCE") "±1%")
        (field (name "AUTHOR") "CERN DEM JLC")
      )
      (libsource (lib "Resistors") (part "Resistor - 1%"))
    )
    (comp (ref "R51")
      (value "10k")
      (footprint "RESC1005X40N")
      (description "Resistor - 1%")
      (fields
        (field (name "PART NUMBER") "R0402_10K_1%_0.0625W_100PPM")
        (field (name "POWER") "0.0625W")
        (field (name "AUTHOR") "CERN DEM JLC")
      )
      (libsource (lib "Resistors") (part "Resistor - 1%"))
    )
    (comp (ref "R52")
      (value "10k")
      (footprint "RESC1005X40N")
      (description "Resistor - 1%")
      (fields
        (field (name "PART NUMBER") "R0402_10K_1%_0.0625W_100PPM")
        (field (name "POWER") "0.0625W")
        (field (name "AUTHOR") "CERN DEM JLC")
      )
      (libsource (lib "Resistors") (part "Resistor - 1%"))
    )
    (comp (ref "R53")
      (value "10k")
      (footprint "RESC1005X40N")
      (description "Resistor - 1%")
      (fields
        (field (name "PART NUMBER") "R0402_10K_1%_0.0625W_100PPM")
        (field (name "POWER") "0.0625W")
        (field (name "AUTHOR") "CERN DEM JLC")
      )
      (libsource (lib "Resistors") (part "Resistor - 1%"))
    )
    (comp (ref "R54")
      (value "10k")
      (footprint "RESC1005X40N")
      (description "Resistor - 1%")
      (fields
        (field (name "PART NUMBER") "R0402_10K_1%_0.0625W_100PPM")
        (field (name "POWER") "0.0625W")
        (field (name "AUTHOR") "CERN DEM JLC")
      )
      (libsource (lib "Resistors") (part "Resistor - 1%"))
    )
    (comp (ref "R55")
      (value "10k")
      (footprint "RESC1005X40N")
      (description "Resistor - 1%")
      (fields
        (field (name "PART NUMBER") "R0402_10K_1%_0.0625W_100PPM")
        (field (name "POWER") "0.0625W")
        (field (name "AUTHOR") "CERN DEM JLC")
      )
      (libsource (lib "Resistors") (part "Resistor - 1%"))
    )
    (comp (ref "R56")
      (value "10k")
      (footprint "RESC1005X40N")
      (description "Resistor - 1%")
      (fields
        (field (name "PART NUMBER") "R0402_10K_1%_0.0625W_100PPM")
        (field (name "POWER") "0.0625W")
        (field (name "AUTHOR") "CERN DEM JLC")
      )
      (libsource (lib "Resistors") (part "Resistor - 1%"))
    )
    (comp (ref "R57")
      (value "10k")
      (footprint "RESC1005X40N")
      (description "Resistor - 1%")
      (fields
        (field (name "PART NUMBER") "R0402_10K_1%_0.0625W_100PPM")
        (field (name "POWER") "0.0625W")
        (field (name "AUTHOR") "CERN DEM JLC")
      )
      (libsource (lib "Resistors") (part "Resistor - 1%"))
    )
    (comp (ref "R58")
      (value "10k")
      (footprint "RESC1005X40N")
      (description "Resistor - 1%")
      (fields
        (field (name "PART NUMBER") "R0402_10K_1%_0.0625W_100PPM")
        (field (name "POWER") "0.0625W")
        (field (name "AUTHOR") "CERN DEM JLC")
      )
      (libsource (lib "Resistors") (part "Resistor - 1%"))
    )
    (comp (ref "R59")
      (value "10k")
      (footprint "RESC1005X40N")
      (description "Resistor - 1%")
      (fields
        (field (name "PART NUMBER") "R0402_10K_1%_0.0625W_100PPM")
        (field (name "POWER") "0.0625W")
        (field (name "AUTHOR") "CERN DEM JLC")
      )
      (libsource (lib "Resistors") (part "Resistor - 1%"))
    )
    (comp (ref "R60")
      (value "10k")
      (footprint "RESC1005X40N")
      (description "Resistor - 1%")
      (fields
        (field (name "PART NUMBER") "R0402_10K_1%_0.0625W_100PPM")
        (field (name "POWER") "0.0625W")
        (field (name "AUTHOR") "CERN DEM JLC")
      )
      (libsource (lib "Resistors") (part "Resistor - 1%"))
    )
    (comp (ref "SW1")
      (value "Switch")
      (footprint "SW_OMRON_A6S-2102-H")
      (description "2 Ways SPST DIP Switch")
      (fields
        (field (name "PART NUMBER") "SW_OMRON_A6S-2102-H")
        (field (name "MANUFACTURER") "OMRON")
        (field (name "AUTHOR") "CERN DEM JMW")
      )
      (libsource (lib "Eletro-mechanical") (part "SW 2x SPST DIP Switch"))
    )
    (comp (ref "SW2")
      (value "Switch")
      (footprint "SW_OMRON_A6S-2102-H")
      (description "2 Ways SPST DIP Switch")
      (fields
        (field (name "PART NUMBER") "SW_OMRON_A6S-2102-H")
        (field (name "MANUFACTURER") "OMRON")
        (field (name "AUTHOR") "CERN DEM JMW")
      )
      (libsource (lib "Eletro-mechanical") (part "SW 2x SPST DIP Switch"))
    )
    (comp (ref "SW3")
      (value "Switch")
      (footprint "SW_OMRON_A6S-2102-H")
      (description "2 Ways SPST DIP Switch")
      (fields
        (field (name "PART NUMBER") "SW_OMRON_A6S-2102-H")
        (field (name "MANUFACTURER") "OMRON")
        (field (name "AUTHOR") "CERN DEM JMW")
      )
      (libsource (lib "Eletro-mechanical") (part "SW 2x SPST DIP Switch"))
    )
    (comp (ref "SW4")
      (value "Switch")
      (footprint "SW_OMRON_A6S-2102-H")
      (description "2 Ways SPST DIP Switch")
      (fields
        (field (name "PART NUMBER") "SW_OMRON_A6S-2102-H")
        (field (name "MANUFACTURER") "OMRON")
        (field (name "AUTHOR") "CERN DEM JMW")
      )
      (libsource (lib "Eletro-mechanical") (part "SW 2x SPST DIP Switch"))
    )
    (comp (ref "SW5")
      (value "Switch")
      (footprint "SW_OMRON_A6S-2102-H")
      (description "2 Ways SPST DIP Switch")
      (fields
        (field (name "PART NUMBER") "SW_OMRON_A6S-2102-H")
        (field (name "MANUFACTURER") "OMRON")
        (field (name "AUTHOR") "CERN DEM JMW")
      )
      (libsource (lib "Eletro-mechanical") (part "SW 2x SPST DIP Switch"))
    )
    (comp (ref "T1")
      (value "IRLML6402PBF")
      (footprint "SOT95P237X112-3N")
      (description "P-CHANNEL MOSFET WITH ZENER DIODE")
      (fields (field (name "MANUFACTURER") "INTERNATIONAL RECTIFIER") (field (name "AUTHOR") "CERN DEM JLC"))
      (libsource (lib "ICs And Semiconductors") (part "P-MOSFET-DZ 1G 2S 3D"))
    )
    (comp (ref "T2")
      (value "IRLML6402PBF")
      (footprint "SOT95P237X112-3N")
      (description "P-CHANNEL MOSFET WITH ZENER DIODE")
      (fields (field (name "MANUFACTURER") "INTERNATIONAL RECTIFIER") (field (name "AUTHOR") "CERN DEM JLC"))
      (libsource (lib "ICs And Semiconductors") (part "P-MOSFET-DZ 1G 2S 3D"))
    )
    (comp (ref "T3")
      (value "IRLML6402PBF")
      (footprint "SOT95P237X112-3N")
      (description "P-CHANNEL MOSFET WITH ZENER DIODE")
      (fields (field (name "MANUFACTURER") "INTERNATIONAL RECTIFIER") (field (name "AUTHOR") "CERN DEM JLC"))
      (libsource (lib "ICs And Semiconductors") (part "P-MOSFET-DZ 1G 2S 3D"))
    )
    (comp (ref "T4")
      (value "IRLML6402PBF")
      (footprint "SOT95P237X112-3N")
      (description "P-CHANNEL MOSFET WITH ZENER DIODE")
      (fields (field (name "MANUFACTURER") "INTERNATIONAL RECTIFIER") (field (name "AUTHOR") "CERN DEM JLC"))
      (libsource (lib "ICs And Semiconductors") (part "P-MOSFET-DZ 1G 2S 3D"))
    )
    (comp (ref "T5")
      (value "IRLML6402PBF")
      (footprint "SOT95P237X112-3N")
      (description "P-CHANNEL MOSFET WITH ZENER DIODE")
      (fields (field (name "MANUFACTURER") "INTERNATIONAL RECTIFIER") (field (name "AUTHOR") "CERN DEM JLC"))
      (libsource (lib "ICs And Semiconductors") (part "P-MOSFET-DZ 1G 2S 3D"))
    )
    (comp (ref "T6")
      (value "IRLML6402PBF")
      (footprint "SOT95P237X112-3N")
      (description "P-CHANNEL MOSFET WITH ZENER DIODE")
      (fields (field (name "MANUFACTURER") "INTERNATIONAL RECTIFIER") (field (name "AUTHOR") "CERN DEM JLC"))
      (libsource (lib "ICs And Semiconductors") (part "P-MOSFET-DZ 1G 2S 3D"))
    )
    (comp (ref "T7")
      (value "IRLML6402PBF")
      (footprint "SOT95P237X112-3N")
      (description "P-CHANNEL MOSFET WITH ZENER DIODE")
      (fields (field (name "MANUFACTURER") "INTERNATIONAL RECTIFIER") (field (name "AUTHOR") "CERN DEM JLC"))
      (libsource (lib "ICs And Semiconductors") (part "P-MOSFET-DZ 1G 2S 3D"))
    )
    (comp (ref "T8")
      (value "IRLML6402PBF")
      (footprint "SOT95P237X112-3N")
      (description "P-CHANNEL MOSFET WITH ZENER DIODE")
      (fields (field (name "MANUFACTURER") "INTERNATIONAL RECTIFIER") (field (name "AUTHOR") "CERN DEM JLC"))
      (libsource (lib "ICs And Semiconductors") (part "P-MOSFET-DZ 1G 2S 3D"))
    )
    (comp (ref "T9")
      (value "DMN2020LSN-7")
      (footprint "SOT95P285X140-3N")
      (description "20V, 6.9A, N-Channel Enhancement Mode MOSFET")
      (fields (field (name "MANUFACTURER") "DIODES INCORPORATED") (field (name "AUTHOR") "CERN DEM JLC"))
      (libsource (lib "ICs And Semiconductors") (part "DMN2020LSN-7"))
    )
    (comp (ref "T10")
      (value "DMN2020LSN-7")
      (footprint "SOT95P285X140-3N")
      (description "20V, 6.9A, N-Channel Enhancement Mode MOSFET")
      (fields (field (name "MANUFACTURER") "DIODES INCORPORATED") (field (name "AUTHOR") "CERN DEM JLC"))
      (libsource (lib "ICs And Semiconductors") (part "DMN2020LSN-7"))
    )
    (comp (ref "T11")
      (value "DMN2020LSN-7")
      (footprint "SOT95P285X140-3N")
      (description "20V, 6.9A, N-Channel Enhancement Mode MOSFET")
      (fields (field (name "MANUFACTURER") "DIODES INCORPORATED") (field (name "AUTHOR") "CERN DEM JLC"))
      (libsource (lib "ICs And Semiconductors") (part "DMN2020LSN-7"))
    )
    (comp (ref "T12")
      (value "DMN2020LSN-7")
      (footprint "SOT95P285X140-3N")
      (description "20V, 6.9A, N-Channel Enhancement Mode MOSFET")
      (fields (field (name "MANUFACTURER") "DIODES INCORPORATED") (field (name "AUTHOR") "CERN DEM JLC"))
      (libsource (lib "ICs And Semiconductors") (part "DMN2020LSN-7"))
    )
    (comp (ref "T13")
      (value "DMN2020LSN-7")
      (footprint "SOT95P285X140-3N")
      (description "20V, 6.9A, N-Channel Enhancement Mode MOSFET")
      (fields (field (name "MANUFACTURER") "DIODES INCORPORATED") (field (name "AUTHOR") "CERN DEM JLC"))
      (libsource (lib "ICs And Semiconductors") (part "DMN2020LSN-7"))
    )
    (comp (ref "T14")
      (value "DMN2020LSN-7")
      (footprint "SOT95P285X140-3N")
      (description "20V, 6.9A, N-Channel Enhancement Mode MOSFET")
      (fields (field (name "MANUFACTURER") "DIODES INCORPORATED") (field (name "AUTHOR") "CERN DEM JLC"))
      (libsource (lib "ICs And Semiconductors") (part "DMN2020LSN-7"))
    )
    (comp (ref "TP6")
      (value "Test Point")
      (footprint "TPS127")
      (fields (field (name "PART NUMBER") "SMD_PAD_1.27X1.27MM") (field (name "AUTHOR") "CERN DEM JLC"))
      (libsource (lib "Eletro-mechanical") (part "Test Point"))
    )
    (comp (ref "TP7")
      (value "Test Point")
      (footprint "TPS127")
      (fields (field (name "PART NUMBER") "SMD_PAD_1.27X1.27MM") (field (name "AUTHOR") "CERN DEM JLC"))
      (libsource (lib "Eletro-mechanical") (part "Test Point"))
    )
    (comp (ref "TP8")
      (value "Test Point")
      (footprint "TPS127")
      (fields (field (name "PART NUMBER") "SMD_PAD_1.27X1.27MM") (field (name "AUTHOR") "CERN DEM JLC"))
      (libsource (lib "Eletro-mechanical") (part "Test Point"))
    )
    (comp (ref "TP9")
      (value "Test Point")
      (footprint "TPS127")
      (fields (field (name "PART NUMBER") "SMD_PAD_1.27X1.27MM") (field (name "AUTHOR") "CERN DEM JLC"))
      (libsource (lib "Eletro-mechanical") (part "Test Point"))
    )
    (comp (ref "TP10")
      (value "Test Point")
      (footprint "TPS127")
      (fields (field (name "PART NUMBER") "SMD_PAD_1.27X1.27MM") (field (name "AUTHOR") "CERN DEM JLC"))
      (libsource (lib "Eletro-mechanical") (part "Test Point"))
    )
    (comp (ref "TR21")
      (value "1:2")
      (footprint "XFMR_MINI-CIRCUITS_DB1627")
      (description "50 OHMS 10 to 4000 MHz RF Transformer")
      (fields
        (field (name "PART NUMBER") "XFMR_MINI-CIRCUITS_TCM2-43X+")
        (field (name "POWER") "0.4W")
        (field (name "AUTHOR") "CERN DEM BC")
      )
      (libsource (lib "Inductors & Transformers") (part "XFMR_MINI-CIRCUITS_TCM2-43X"))
    )
    (comp (ref "TR22")
      (value "1:2")
      (footprint "XFMR_MINI-CIRCUITS_DB1627")
      (description "50 OHMS 10 to 4000 MHz RF Transformer")
      (fields
        (field (name "PART NUMBER") "XFMR_MINI-CIRCUITS_TCM2-43X+")
        (field (name "POWER") "0.4W")
        (field (name "AUTHOR") "CERN DEM BC")
      )
      (libsource (lib "Inductors & Transformers") (part "XFMR_MINI-CIRCUITS_TCM2-43X"))
    )
  )
  (nets
    (net (code "1") (name "/ADC0") (class "Default")
      (node (ref "J33") (pin "1") (pinfunction "1_1") (pintype "bidirectional"))
    )
    (net (code "2") (name "/ADC1") (class "Default")
      (node (ref "J36") (pin "1") (pinfunction "1_1") (pintype "bidirectional"))
    )
    (net (code "3") (name "/ADC2") (class "Default")
      (node (ref "J37") (pin "1") (pinfunction "1_1") (pintype "bidirectional"))
    )
    (net (code "4") (name "/ADC3") (class "Default")
      (node (ref "J38") (pin "1") (pinfunction "1_1") (pintype "bidirectional"))
    )
    (net (code "5") (name "/DAC0") (class "Default")
      (node (ref "J27") (pin "1") (pinfunction "1_1") (pintype "bidirectional"))
    )
    (net (code "6") (name "/DAC1") (class "Default")
      (node (ref "J28") (pin "1") (pinfunction "1_1") (pintype "bidirectional"))
    )
    (net (code "7") (name "/DAC2") (class "Default")
      (node (ref "J29") (pin "1") (pinfunction "1_1") (pintype "bidirectional"))
    )
    (net (code "8") (name "/DAC3") (class "Default")
      (node (ref "J30") (pin "1") (pinfunction "1_1") (pintype "bidirectional"))
    )
    (net (code "9") (name "/LO") (class "Default")
      (node (ref "J26") (pin "1") (pinfunction "1_1") (pintype "bidirectional"))
    )
    (net (code "10") (name "/LVDS0_N") (class "Default")
      (node (ref "J40") (pin "3") (pinfunction "3_3") (pintype "bidirectional"))
    )
    (net (code "11") (name "/LVDS0_P") (class "Default")
      (node (ref "J40") (pin "2") (pinfunction "2_2") (pintype "bidirectional"))
    )
    (net (code "12") (name "/LVDS1_N") (class "Default")
      (node (ref "J40") (pin "6") (pinfunction "6_6") (pintype "bidirectional"))
    )
    (net (code "13") (name "/LVDS1_P") (class "Default")
      (node (ref "J40") (pin "5") (pinfunction "5_5") (pintype "bidirectional"))
    )
    (net (code "14") (name "/LVDS2_N") (class "Default")
      (node (ref "J40") (pin "9") (pinfunction "9_9") (pintype "bidirectional"))
    )
    (net (code "15") (name "/LVDS2_P") (class "Default")
      (node (ref "J40") (pin "8") (pinfunction "8_8") (pintype "bidirectional"))
    )
    (net (code "16") (name "/LVDS3_N") (class "Default")
      (node (ref "J40") (pin "12") (pinfunction "12_12") (pintype "bidirectional"))
    )
    (net (code "17") (name "/LVDS3_P") (class "Default")
      (node (ref "J40") (pin "11") (pinfunction "11_11") (pintype "bidirectional"))
    )
    (net (code "18") (name "/LVDS4_N") (class "Default")
      (node (ref "J40") (pin "15") (pinfunction "15_15") (pintype "bidirectional"))
    )
    (net (code "19") (name "/LVDS4_P") (class "Default")
      (node (ref "J40") (pin "14") (pinfunction "14_14") (pintype "bidirectional"))
    )
    (net (code "20") (name "/LVDS5_N") (class "Default")
      (node (ref "J40") (pin "18") (pinfunction "18_18") (pintype "bidirectional"))
    )
    (net (code "21") (name "/LVDS5_P") (class "Default")
      (node (ref "J40") (pin "17") (pinfunction "17_17") (pintype "bidirectional"))
    )
    (net (code "22") (name "/LVDS6_N") (class "Default")
      (node (ref "J40") (pin "21") (pinfunction "21_21") (pintype "bidirectional"))
    )
    (net (code "23") (name "/LVDS6_P") (class "Default")
      (node (ref "J40") (pin "20") (pinfunction "20_20") (pintype "bidirectional"))
    )
    (net (code "24") (name "/LVDS7_N") (class "Default")
      (node (ref "J40") (pin "24") (pinfunction "24_24") (pintype "bidirectional"))
    )
    (net (code "25") (name "/LVDS7_P") (class "Default")
      (node (ref "J40") (pin "23") (pinfunction "23_23") (pintype "bidirectional"))
    )
    (net (code "26") (name "/MEZZ1_IO0") (class "Default")
      (node (ref "IC4") (pin "1") (pinfunction "P00_1") (pintype "bidirectional"))
    )
    (net (code "27") (name "/MEZZ1_IO1") (class "Default")
      (node (ref "IC4") (pin "2") (pinfunction "P01_2") (pintype "bidirectional"))
    )
    (net (code "28") (name "/MEZZ1_IO2") (class "Default")
      (node (ref "IC4") (pin "3") (pinfunction "P02_3") (pintype "bidirectional"))
    )
    (net (code "29") (name "/MEZZ1_IO3") (class "Default")
      (node (ref "IC4") (pin "4") (pinfunction "P03_4") (pintype "bidirectional"))
    )
    (net (code "30") (name "/MEZZ1_IO4") (class "Default")
      (node (ref "IC4") (pin "5") (pinfunction "P04_5") (pintype "bidirectional"))
    )
    (net (code "31") (name "/MEZZ1_IO5") (class "Default")
      (node (ref "IC4") (pin "6") (pinfunction "P05_6") (pintype "bidirectional"))
    )
    (net (code "32") (name "/MEZZ1_IO6") (class "Default")
      (node (ref "IC4") (pin "7") (pinfunction "P06_7") (pintype "bidirectional"))
    )
    (net (code "33") (name "/MEZZ1_IO7") (class "Default")
      (node (ref "IC4") (pin "8") (pinfunction "P07_8") (pintype "bidirectional"))
    )
    (net (code "34") (name "/MEZZ1_IO8") (class "Default")
      (node (ref "IC4") (pin "10") (pinfunction "P10_10") (pintype "bidirectional"))
    )
    (net (code "35") (name "/MEZZ1_IO9") (class "Default")
      (node (ref "IC4") (pin "11") (pinfunction "P11_11") (pintype "bidirectional"))
    )
    (net (code "36") (name "/MEZZ1_IO10") (class "Default")
      (node (ref "IC4") (pin "12") (pinfunction "P12_12") (pintype "bidirectional"))
    )
    (net (code "37") (name "/MEZZ1_IO11") (class "Default")
      (node (ref "IC4") (pin "13") (pinfunction "P13_13") (pintype "bidirectional"))
    )
    (net (code "38") (name "/MEZZ1_IO12") (class "Default")
      (node (ref "IC4") (pin "14") (pinfunction "P14_14") (pintype "bidirectional"))
    )
    (net (code "39") (name "/MEZZ1_IO13") (class "Default")
      (node (ref "IC4") (pin "15") (pinfunction "P15_15") (pintype "bidirectional"))
    )
    (net (code "40") (name "/MEZZ1_IO14") (class "Default")
      (node (ref "IC4") (pin "16") (pinfunction "P16_16") (pintype "bidirectional"))
    )
    (net (code "41") (name "/MEZZ1_IO15") (class "Default")
      (node (ref "IC4") (pin "17") (pinfunction "P17_17") (pintype "bidirectional"))
    )
    (net (code "42") (name "/MEZZ2_IO0") (class "Default")
      (node (ref "IC3") (pin "1") (pinfunction "P00_1") (pintype "bidirectional"))
    )
    (net (code "43") (name "/MEZZ2_IO1") (class "Default")
      (node (ref "IC3") (pin "2") (pinfunction "P01_2") (pintype "bidirectional"))
    )
    (net (code "44") (name "/MEZZ2_IO2") (class "Default")
      (node (ref "IC3") (pin "3") (pinfunction "P02_3") (pintype "bidirectional"))
    )
    (net (code "45") (name "/MEZZ2_IO3") (class "Default")
      (node (ref "IC3") (pin "4") (pinfunction "P03_4") (pintype "bidirectional"))
    )
    (net (code "46") (name "/MEZZ2_IO4") (class "Default")
      (node (ref "IC3") (pin "5") (pinfunction "P04_5") (pintype "bidirectional"))
    )
    (net (code "47") (name "/MEZZ2_IO5") (class "Default")
      (node (ref "IC3") (pin "6") (pinfunction "P05_6") (pintype "bidirectional"))
    )
    (net (code "48") (name "/MEZZ2_IO6") (class "Default")
      (node (ref "IC3") (pin "7") (pinfunction "P06_7") (pintype "bidirectional"))
    )
    (net (code "49") (name "/MEZZ2_IO7") (class "Default")
      (node (ref "IC3") (pin "8") (pinfunction "P07_8") (pintype "bidirectional"))
    )
    (net (code "50") (name "/MEZZ2_IO8") (class "Default")
      (node (ref "IC3") (pin "10") (pinfunction "P10_10") (pintype "bidirectional"))
    )
    (net (code "51") (name "/MEZZ2_IO9") (class "Default")
      (node (ref "IC3") (pin "11") (pinfunction "P11_11") (pintype "bidirectional"))
    )
    (net (code "52") (name "/MEZZ2_IO10") (class "Default")
      (node (ref "IC3") (pin "12") (pinfunction "P12_12") (pintype "bidirectional"))
    )
    (net (code "53") (name "/MEZZ2_IO11") (class "Default")
      (node (ref "IC3") (pin "13") (pinfunction "P13_13") (pintype "bidirectional"))
    )
    (net (code "54") (name "/MEZZ2_IO12") (class "Default")
      (node (ref "IC3") (pin "14") (pinfunction "P14_14") (pintype "bidirectional"))
    )
    (net (code "55") (name "/MEZZ2_IO13") (class "Default")
      (node (ref "IC3") (pin "15") (pinfunction "P15_15") (pintype "bidirectional"))
    )
    (net (code "56") (name "/MEZZ2_IO14") (class "Default")
      (node (ref "IC3") (pin "16") (pinfunction "P16_16") (pintype "bidirectional"))
    )
    (net (code "57") (name "/MEZZ2_IO15") (class "Default")
      (node (ref "IC3") (pin "17") (pinfunction "P17_17") (pintype "bidirectional"))
    )
    (net (code "58") (name "/SCL1") (class "Default")
      (node (ref "IC1") (pin "1") (pinfunction "SCL_1") (pintype "input"))
      (node (ref "IC2") (pin "19") (pinfunction "SCL_19") (pintype "input"))
      (node (ref "IC4") (pin "19") (pinfunction "SCL_19") (pintype "input"))
      (node (ref "J40") (pin "27") (pinfunction "27_27") (pintype "bidirectional"))
    )
    (net (code "59") (name "/SCL2") (class "Default")
      (node (ref "IC3") (pin "19") (pinfunction "SCL_19") (pintype "input"))
      (node (ref "IC5") (pin "1") (pinfunction "SCL_1") (pintype "input"))
    )
    (net (code "60") (name "/SDA1") (class "Default")
      (node (ref "IC1") (pin "3") (pinfunction "SDA_3") (pintype "bidirectional"))
      (node (ref "IC2") (pin "20") (pinfunction "SDA_20") (pintype "bidirectional"))
      (node (ref "IC4") (pin "20") (pinfunction "SDA_20") (pintype "bidirectional"))
      (node (ref "J40") (pin "26") (pinfunction "26_26") (pintype "bidirectional"))
    )
    (net (code "61") (name "/SDA2") (class "Default")
      (node (ref "IC3") (pin "20") (pinfunction "SDA_20") (pintype "bidirectional"))
      (node (ref "IC5") (pin "3") (pinfunction "SDA_3") (pintype "bidirectional"))
    )
    (net (code "62") (name "/SW1") (class "Default")
      (node (ref "IC2") (pin "1") (pinfunction "P00_1") (pintype "bidirectional"))
      (node (ref "R43") (pin "1") (pinfunction "1_1") (pintype "passive"))
      (node (ref "T9") (pin "1") (pinfunction "G_1") (pintype "passive"))
    )
    (net (code "63") (name "/SW2") (class "Default")
      (node (ref "IC2") (pin "2") (pinfunction "P01_2") (pintype "bidirectional"))
      (node (ref "R44") (pin "1") (pinfunction "1_1") (pintype "passive"))
      (node (ref "T10") (pin "1") (pinfunction "G_1") (pintype "passive"))
    )
    (net (code "64") (name "/SW3") (class "Default")
      (node (ref "IC2") (pin "3") (pinfunction "P02_3") (pintype "bidirectional"))
      (node (ref "R45") (pin "1") (pinfunction "1_1") (pintype "passive"))
      (node (ref "T11") (pin "1") (pinfunction "G_1") (pintype "passive"))
    )
    (net (code "65") (name "/SW4") (class "Default")
      (node (ref "IC2") (pin "4") (pinfunction "P03_4") (pintype "bidirectional"))
      (node (ref "R46") (pin "1") (pinfunction "1_1") (pintype "passive"))
      (node (ref "T12") (pin "1") (pinfunction "G_1") (pintype "passive"))
    )
    (net (code "66") (name "/SW5") (class "Default")
      (node (ref "IC2") (pin "5") (pinfunction "P04_5") (pintype "bidirectional"))
      (node (ref "R19") (pin "1") (pinfunction "1_1") (pintype "passive"))
      (node (ref "T3") (pin "1") (pinfunction "G_1") (pintype "passive"))
    )
    (net (code "67") (name "/SW6") (class "Default")
      (node (ref "IC2") (pin "6") (pinfunction "P05_6") (pintype "bidirectional"))
      (node (ref "R20") (pin "1") (pinfunction "1_1") (pintype "passive"))
      (node (ref "T4") (pin "1") (pinfunction "G_1") (pintype "passive"))
    )
    (net (code "68") (name "/SW7") (class "Default")
      (node (ref "IC2") (pin "7") (pinfunction "P06_7") (pintype "bidirectional"))
      (node (ref "R47") (pin "1") (pinfunction "1_1") (pintype "passive"))
      (node (ref "T13") (pin "1") (pinfunction "G_1") (pintype "passive"))
    )
    (net (code "69") (name "/SW8") (class "Default")
      (node (ref "IC2") (pin "8") (pinfunction "P07_8") (pintype "bidirectional"))
      (node (ref "R48") (pin "1") (pinfunction "1_1") (pintype "passive"))
      (node (ref "T14") (pin "1") (pinfunction "G_1") (pintype "passive"))
    )
    (net (code "70") (name "/SW9") (class "Default")
      (node (ref "IC2") (pin "10") (pinfunction "P10_10") (pintype "bidirectional"))
      (node (ref "R17") (pin "1") (pinfunction "1_1") (pintype "passive"))
      (node (ref "T1") (pin "1") (pinfunction "G_1") (pintype "passive"))
    )
    (net (code "71") (name "/SW10") (class "Default")
      (node (ref "IC2") (pin "11") (pinfunction "P11_11") (pintype "bidirectional"))
      (node (ref "R18") (pin "1") (pinfunction "1_1") (pintype "passive"))
      (node (ref "T2") (pin "1") (pinfunction "G_1") (pintype "passive"))
    )
    (net (code "72") (name "/TEST_SMA_N") (class "Default")
      (node (ref "C25") (pin "1") (pinfunction "1_1") (pintype "passive"))
      (node (ref "C44") (pin "1") (pinfunction "1_1") (pintype "passive"))
      (node (ref "TR21") (pin "6") (pinfunction "S1_6") (pintype "passive"))
      (node (ref "TR22") (pin "4") (pinfunction "S1_4") (pintype "passive"))
    )
    (net (code "73") (name "/TEST_SMA_P") (class "Default")
      (node (ref "C23") (pin "1") (pinfunction "1_1") (pintype "passive"))
      (node (ref "C24") (pin "1") (pinfunction "1_1") (pintype "passive"))
      (node (ref "TR21") (pin "4") (pinfunction "S1_4") (pintype "passive"))
      (node (ref "TR22") (pin "6") (pinfunction "S1_6") (pintype "passive"))
    )
    (net (code "74") (name "GND") (class "Default")
      (node (ref "C23") (pin "2") (pinfunction "2_2") (pintype "passive"))
      (node (ref "C24") (pin "2") (pinfunction "2_2") (pintype "passive"))
      (node (ref "C25") (pin "2") (pinfunction "2_2") (pintype "passive"))
      (node (ref "C44") (pin "2") (pinfunction "2_2") (pintype "passive"))
      (node (ref "C45") (pin "1") (pinfunction "1_1") (pintype "passive"))
      (node (ref "C46") (pin "1") (pinfunction "1_1") (pintype "passive"))
      (node (ref "C47") (pin "1") (pinfunction "1_1") (pintype "passive"))
      (node (ref "IC1") (pin "2") (pinfunction "VSS_2") (pintype "power_in"))
      (node (ref "IC2") (pin "23") (pinfunction "A1_23") (pintype "bidirectional"))
      (node (ref "IC2") (pin "9") (pinfunction "GND_9") (pintype "power_in"))
      (node (ref "IC3") (pin "18") (pinfunction "A0_18") (pintype "bidirectional"))
      (node (ref "IC3") (pin "23") (pinfunction "A1_23") (pintype "bidirectional"))
      (node (ref "IC3") (pin "9") (pinfunction "GND_9") (pintype "power_in"))
      (node (ref "IC4") (pin "18") (pinfunction "A0_18") (pintype "bidirectional"))
      (node (ref "IC4") (pin "23") (pinfunction "A1_23") (pintype "bidirectional"))
      (node (ref "IC4") (pin "9") (pinfunction "GND_9") (pintype "power_in"))
      (node (ref "IC5") (pin "2") (pinfunction "VSS_2") (pintype "power_in"))
      (node (ref "J26") (pin "2") (pinfunction "2_2") (pintype "bidirectional"))
      (node (ref "J27") (pin "2") (pinfunction "2_2") (pintype "bidirectional"))
      (node (ref "J28") (pin "2") (pinfunction "2_2") (pintype "bidirectional"))
      (node (ref "J29") (pin "2") (pinfunction "2_2") (pintype "bidirectional"))
      (node (ref "J30") (pin "2") (pinfunction "2_2") (pintype "bidirectional"))
      (node (ref "J31") (pin "2") (pinfunction "2_2") (pintype "bidirectional"))
      (node (ref "J32") (pin "2") (pinfunction "2_2") (pintype "bidirectional"))
      (node (ref "J33") (pin "2") (pinfunction "2_2") (pintype "bidirectional"))
      (node (ref "J34") (pin "2") (pinfunction "2_2") (pintype "bidirectional"))
      (node (ref "J35") (pin "2") (pinfunction "2_2") (pintype "bidirectional"))
      (node (ref "J36") (pin "2") (pinfunction "2_2") (pintype "bidirectional"))
      (node (ref "J37") (pin "2") (pinfunction "2_2") (pintype "bidirectional"))
      (node (ref "J38") (pin "2") (pinfunction "2_2") (pintype "bidirectional"))
      (node (ref "J39") (pin "2") (pinfunction "2_2") (pintype "bidirectional"))
      (node (ref "J40") (pin "1") (pinfunction "1_1") (pintype "bidirectional"))
      (node (ref "J40") (pin "10") (pinfunction "10_10") (pintype "bidirectional"))
      (node (ref "J40") (pin "13") (pinfunction "13_13") (pintype "bidirectional"))
      (node (ref "J40") (pin "16") (pinfunction "16_16") (pintype "bidirectional"))
      (node (ref "J40") (pin "19") (pinfunction "19_19") (pintype "bidirectional"))
      (node (ref "J40") (pin "22") (pinfunction "22_22") (pintype "bidirectional"))
      (node (ref "J40") (pin "25") (pinfunction "25_25") (pintype "bidirectional"))
      (node (ref "J40") (pin "4") (pinfunction "4_4") (pintype "bidirectional"))
      (node (ref "J40") (pin "7") (pinfunction "7_7") (pintype "bidirectional"))
      (node (ref "J41") (pin "2") (pinfunction "2_2") (pintype "bidirectional"))
      (node (ref "LD1") (pin "2") (pinfunction "A_2") (pintype "passive"))
      (node (ref "LD2") (pin "1") (pinfunction "C_1") (pintype "passive"))
      (node (ref "LD3") (pin "1") (pinfunction "C_1") (pintype "passive"))
      (node (ref "LD4") (pin "1") (pinfunction "C_1") (pintype "passive"))
      (node (ref "LD5") (pin "1") (pinfunction "C_1") (pintype "passive"))
      (node (ref "LD6") (pin "1") (pinfunction "C_1") (pintype "passive"))
      (node (ref "LD7") (pin "1") (pinfunction "C_1") (pintype "passive"))
      (node (ref "LD8") (pin "1") (pinfunction "C_1") (pintype "passive"))
      (node (ref "R17") (pin "2") (pinfunction "2_2") (pintype "passive"))
      (node (ref "R18") (pin "2") (pinfunction "2_2") (pintype "passive"))
      (node (ref "R19") (pin "2") (pinfunction "2_2") (pintype "passive"))
      (node (ref "R20") (pin "2") (pinfunction "2_2") (pintype "passive"))
      (node (ref "R43") (pin "2") (pinfunction "2_2") (pintype "passive"))
      (node (ref "R44") (pin "2") (pinfunction "2_2") (pintype "passive"))
      (node (ref "R45") (pin "2") (pinfunction "2_2") (pintype "passive"))
      (node (ref "R46") (pin "2") (pinfunction "2_2") (pintype "passive"))
      (node (ref "R47") (pin "2") (pinfunction "2_2") (pintype "passive"))
      (node (ref "R48") (pin "2") (pinfunction "2_2") (pintype "passive"))
      (node (ref "SW1") (pin "3") (pinfunction "3_3") (pintype "passive"))
      (node (ref "SW1") (pin "4") (pinfunction "4_4") (pintype "passive"))
      (node (ref "SW2") (pin "3") (pinfunction "3_3") (pintype "passive"))
      (node (ref "SW2") (pin "4") (pinfunction "4_4") (pintype "passive"))
      (node (ref "SW3") (pin "3") (pinfunction "3_3") (pintype "passive"))
      (node (ref "SW3") (pin "4") (pinfunction "4_4") (pintype "passive"))
      (node (ref "SW4") (pin "3") (pinfunction "3_3") (pintype "passive"))
      (node (ref "SW4") (pin "4") (pinfunction "4_4") (pintype "passive"))
      (node (ref "SW5") (pin "3") (pinfunction "3_3") (pintype "passive"))
      (node (ref "SW5") (pin "4") (pinfunction "4_4") (pintype "passive"))
      (node (ref "T10") (pin "2") (pinfunction "S_2") (pintype "passive"))
      (node (ref "T11") (pin "2") (pinfunction "S_2") (pintype "passive"))
      (node (ref "T12") (pin "2") (pinfunction "S_2") (pintype "passive"))
      (node (ref "T13") (pin "2") (pinfunction "S_2") (pintype "passive"))
      (node (ref "T14") (pin "2") (pinfunction "S_2") (pintype "passive"))
      (node (ref "T5") (pin "2") (pinfunction "S_2") (pintype "passive"))
      (node (ref "T6") (pin "2") (pinfunction "S_2") (pintype "passive"))
      (node (ref "T7") (pin "2") (pinfunction "S_2") (pintype "passive"))
      (node (ref "T8") (pin "2") (pinfunction "S_2") (pintype "passive"))
      (node (ref "T9") (pin "2") (pinfunction "S_2") (pintype "passive"))
      (node (ref "TR21") (pin "1") (pinfunction "P1_1") (pintype "passive"))
      (node (ref "TR21") (pin "2") (pinfunction "P1_2") (pintype "passive"))
      (node (ref "TR21") (pin "5") (pinfunction "NC_5") (pintype "passive"))
      (node (ref "TR22") (pin "1") (pinfunction "P1_1") (pintype "passive"))
      (node (ref "TR22") (pin "2") (pinfunction "P1_2") (pintype "passive"))
      (node (ref "TR22") (pin "5") (pinfunction "NC_5") (pintype "passive"))
    )
    (net (code "75") (name "N6V0A") (class "Default")
      (node (ref "R23") (pin "2") (pinfunction "2_2") (pintype "passive"))
      (node (ref "R24") (pin "2") (pinfunction "2_2") (pintype "passive"))
      (node (ref "R37") (pin "1") (pinfunction "1_1") (pintype "passive"))
      (node (ref "R39") (pin "1") (pinfunction "1_1") (pintype "passive"))
      (node (ref "R56") (pin "2") (pinfunction "2_2") (pintype "passive"))
      (node (ref "TP9") (pin "1") (pinfunction "1_1") (pintype "bidirectional"))
    )
    (net (code "76") (name "N12V0A") (class "Default")
      (node (ref "R21") (pin "1") (pinfunction "1_1") (pintype "passive"))
      (node (ref "R25") (pin "2") (pinfunction "2_2") (pintype "passive"))
      (node (ref "R26") (pin "2") (pinfunction "2_2") (pintype "passive"))
      (node (ref "R27") (pin "1") (pinfunction "1_1") (pintype "passive"))
      (node (ref "R53") (pin "1") (pinfunction "1_1") (pintype "passive"))
      (node (ref "TP7") (pin "1") (pinfunction "1_1") (pintype "bidirectional"))
    )
    (net (code "77") (name "Net-(J31-Pad1)") (class "Default")
      (node (ref "J31") (pin "1") (pinfunction "1_1") (pintype "bidirectional"))
      (node (ref "J32") (pin "1") (pinfunction "1_1") (pintype "bidirectional"))
    )
    (net (code "78") (name "Net-(J34-Pad1)") (class "Default")
      (node (ref "J34") (pin "1") (pinfunction "1_1") (pintype "bidirectional"))
      (node (ref "J35") (pin "1") (pinfunction "1_1") (pintype "bidirectional"))
    )
    (net (code "79") (name "Net-(J39-Pad1)") (class "Default")
      (node (ref "J39") (pin "1") (pinfunction "1_1") (pintype "bidirectional"))
      (node (ref "TR21") (pin "3") (pinfunction "P1_3") (pintype "passive"))
    )
    (net (code "80") (name "Net-(J41-Pad1)") (class "Default")
      (node (ref "J41") (pin "1") (pinfunction "1_1") (pintype "bidirectional"))
      (node (ref "TR22") (pin "3") (pinfunction "P1_3") (pintype "passive"))
    )
    (net (code "81") (name "Net-(LD1-C)") (class "Default")
      (node (ref "LD1") (pin "1") (pinfunction "C_1") (pintype "passive"))
      (node (ref "R54") (pin "1") (pinfunction "1_1") (pintype "passive"))
    )
    (net (code "82") (name "Net-(LD2-A)") (class "Default")
      (node (ref "LD2") (pin "2") (pinfunction "A_2") (pintype "passive"))
      (node (ref "R59") (pin "1") (pinfunction "1_1") (pintype "passive"))
      (node (ref "R60") (pin "1") (pinfunction "1_1") (pintype "passive"))
    )
    (net (code "83") (name "Net-(LD4-A)") (class "Default")
      (node (ref "LD4") (pin "2") (pinfunction "A_2") (pintype "passive"))
      (node (ref "R57") (pin "1") (pinfunction "1_1") (pintype "passive"))
      (node (ref "R58") (pin "1") (pinfunction "1_1") (pintype "passive"))
    )
    (net (code "84") (name "Net-(LD6-A)") (class "Default")
      (node (ref "LD6") (pin "2") (pinfunction "A_2") (pintype "passive"))
      (node (ref "R55") (pin "1") (pinfunction "1_1") (pintype "passive"))
    )
    (net (code "85") (name "Net-(LD7-A)") (class "Default")
      (node (ref "LD7") (pin "2") (pinfunction "A_2") (pintype "passive"))
      (node (ref "R52") (pin "2") (pinfunction "2_2") (pintype "passive"))
    )
    (net (code "86") (name "Net-(LD8-A)") (class "Default")
      (node (ref "LD8") (pin "2") (pinfunction "A_2") (pintype "passive"))
      (node (ref "R56") (pin "1") (pinfunction "1_1") (pintype "passive"))
    )
    (net (code "87") (name "Net-(R11-Pad2)") (class "Default")
      (node (ref "R11") (pin "2") (pinfunction "2_2") (pintype "passive"))
      (node (ref "R12") (pin "1") (pinfunction "1_1") (pintype "passive"))
    )
    (net (code "88") (name "Net-(R12-Pad2)") (class "Default")
      (node (ref "R12") (pin "2") (pinfunction "2_2") (pintype "passive"))
      (node (ref "R13") (pin "1") (pinfunction "1_1") (pintype "passive"))
    )
    (net (code "89") (name "Net-(R14-Pad2)") (class "Default")
      (node (ref "R14") (pin "2") (pinfunction "2_2") (pintype "passive"))
      (node (ref "R15") (pin "1") (pinfunction "1_1") (pintype "passive"))
    )
    (net (code "90") (name "Net-(R15-Pad2)") (class "Default")
      (node (ref "R15") (pin "2") (pinfunction "2_2") (pintype "passive"))
      (node (ref "R16") (pin "1") (pinfunction "1_1") (pintype "passive"))
    )
    (net (code "91") (name "Net-(R21-Pad2)") (class "Default")
      (node (ref "R21") (pin "2") (pinfunction "2_2") (pintype "passive"))
      (node (ref "R22") (pin "1") (pinfunction "1_1") (pintype "passive"))
    )
    (net (code "92") (name "Net-(R27-Pad2)") (class "Default")
      (node (ref "R27") (pin "2") (pinfunction "2_2") (pintype "passive"))
      (node (ref "R28") (pin "1") (pinfunction "1_1") (pintype "passive"))
    )
    (net (code "93") (name "Net-(R29-Pad2)") (class "Default")
      (node (ref "R29") (pin "2") (pinfunction "2_2") (pintype "passive"))
      (node (ref "R30") (pin "1") (pinfunction "1_1") (pintype "passive"))
    )
    (net (code "94") (name "Net-(R30-Pad2)") (class "Default")
      (node (ref "R30") (pin "2") (pinfunction "2_2") (pintype "passive"))
      (node (ref "R31") (pin "1") (pinfunction "1_1") (pintype "passive"))
    )
    (net (code "95") (name "Net-(R31-Pad2)") (class "Default")
      (node (ref "R31") (pin "2") (pinfunction "2_2") (pintype "passive"))
      (node (ref "R32") (pin "1") (pinfunction "1_1") (pintype "passive"))
    )
    (net (code "96") (name "Net-(R33-Pad2)") (class "Default")
      (node (ref "R33") (pin "2") (pinfunction "2_2") (pintype "passive"))
      (node (ref "R34") (pin "1") (pinfunction "1_1") (pintype "passive"))
    )
    (net (code "97") (name "Net-(R34-Pad2)") (class "Default")
      (node (ref "R34") (pin "2") (pinfunction "2_2") (pintype "passive"))
      (node (ref "R35") (pin "1") (pinfunction "1_1") (pintype "passive"))
    )
    (net (code "98") (name "Net-(R35-Pad2)") (class "Default")
      (node (ref "R35") (pin "2") (pinfunction "2_2") (pintype "passive"))
      (node (ref "R36") (pin "1") (pinfunction "1_1") (pintype "passive"))
    )
    (net (code "99") (name "Net-(R37-Pad2)") (class "Default")
      (node (ref "R37") (pin "2") (pinfunction "2_2") (pintype "passive"))
      (node (ref "R38") (pin "1") (pinfunction "1_1") (pintype "passive"))
    )
    (net (code "100") (name "Net-(R39-Pad2)") (class "Default")
      (node (ref "R39") (pin "2") (pinfunction "2_2") (pintype "passive"))
      (node (ref "R40") (pin "1") (pinfunction "1_1") (pintype "passive"))
    )
    (net (code "101") (name "Net-(R41-Pad2)") (class "Default")
      (node (ref "R41") (pin "2") (pinfunction "2_2") (pintype "passive"))
      (node (ref "R42") (pin "1") (pinfunction "1_1") (pintype "passive"))
    )
    (net (code "102") (name "Net-(R49-Pad2)") (class "Default")
      (node (ref "R49") (pin "2") (pinfunction "2_2") (pintype "passive"))
      (node (ref "R50") (pin "1") (pinfunction "1_1") (pintype "passive"))
    )
    (net (code "103") (name "Net-(R51-Pad2)") (class "Default")
      (node (ref "R51") (pin "2") (pinfunction "2_2") (pintype "passive"))
      (node (ref "R52") (pin "1") (pinfunction "1_1") (pintype "passive"))
    )
    (net (code "104") (name "Net-(R53-Pad2)") (class "Default")
      (node (ref "R53") (pin "2") (pinfunction "2_2") (pintype "passive"))
      (node (ref "R54") (pin "2") (pinfunction "2_2") (pintype "passive"))
    )
    (net (code "105") (name "Net-(T1-D)") (class "Default")
      (node (ref "R23") (pin "1") (pinfunction "1_1") (pintype "passive"))
      (node (ref "T1") (pin "3") (pinfunction "D_3") (pintype "passive"))
      (node (ref "T5") (pin "1") (pinfunction "G_1") (pintype "passive"))
    )
    (net (code "106") (name "Net-(T2-D)") (class "Default")
      (node (ref "R24") (pin "1") (pinfunction "1_1") (pintype "passive"))
      (node (ref "T2") (pin "3") (pinfunction "D_3") (pintype "passive"))
      (node (ref "T6") (pin "1") (pinfunction "G_1") (pintype "passive"))
    )
    (net (code "107") (name "Net-(T3-D)") (class "Default")
      (node (ref "R25") (pin "1") (pinfunction "1_1") (pintype "passive"))
      (node (ref "T3") (pin "3") (pinfunction "D_3") (pintype "passive"))
      (node (ref "T7") (pin "1") (pinfunction "G_1") (pintype "passive"))
    )
    (net (code "108") (name "Net-(T4-D)") (class "Default")
      (node (ref "R26") (pin "1") (pinfunction "1_1") (pintype "passive"))
      (node (ref "T4") (pin "3") (pinfunction "D_3") (pintype "passive"))
      (node (ref "T8") (pin "1") (pinfunction "G_1") (pintype "passive"))
    )
    (net (code "109") (name "Net-(T5-D)") (class "Default")
      (node (ref "R38") (pin "2") (pinfunction "2_2") (pintype "passive"))
      (node (ref "SW4") (pin "1") (pinfunction "1_1") (pintype "passive"))
      (node (ref "T5") (pin "3") (pinfunction "D_3") (pintype "passive"))
    )
    (net (code "110") (name "Net-(T6-D)") (class "Default")
      (node (ref "R40") (pin "2") (pinfunction "2_2") (pintype "passive"))
      (node (ref "SW4") (pin "2") (pinfunction "2_2") (pintype "passive"))
      (node (ref "T6") (pin "3") (pinfunction "D_3") (pintype "passive"))
    )
    (net (code "111") (name "Net-(T7-D)") (class "Default")
      (node (ref "R22") (pin "2") (pinfunction "2_2") (pintype "passive"))
      (node (ref "SW2") (pin "1") (pinfunction "1_1") (pintype "passive"))
      (node (ref "T7") (pin "3") (pinfunction "D_3") (pintype "passive"))
    )
    (net (code "112") (name "Net-(T8-D)") (class "Default")
      (node (ref "R28") (pin "2") (pinfunction "2_2") (pintype "passive"))
      (node (ref "SW2") (pin "2") (pinfunction "2_2") (pintype "passive"))
      (node (ref "T8") (pin "3") (pinfunction "D_3") (pintype "passive"))
    )
    (net (code "113") (name "Net-(T9-D)") (class "Default")
      (node (ref "R50") (pin "2") (pinfunction "2_2") (pintype "passive"))
      (node (ref "SW5") (pin "2") (pinfunction "2_2") (pintype "passive"))
      (node (ref "T9") (pin "3") (pinfunction "D_3") (pintype "passive"))
    )
    (net (code "114") (name "Net-(T10-D)") (class "Default")
      (node (ref "R42") (pin "2") (pinfunction "2_2") (pintype "passive"))
      (node (ref "SW5") (pin "1") (pinfunction "1_1") (pintype "passive"))
      (node (ref "T10") (pin "3") (pinfunction "D_3") (pintype "passive"))
    )
    (net (code "115") (name "Net-(T11-D)") (class "Default")
      (node (ref "R36") (pin "2") (pinfunction "2_2") (pintype "passive"))
      (node (ref "SW3") (pin "2") (pinfunction "2_2") (pintype "passive"))
      (node (ref "T11") (pin "3") (pinfunction "D_3") (pintype "passive"))
    )
    (net (code "116") (name "Net-(T12-D)") (class "Default")
      (node (ref "R32") (pin "2") (pinfunction "2_2") (pintype "passive"))
      (node (ref "SW3") (pin "1") (pinfunction "1_1") (pintype "passive"))
      (node (ref "T12") (pin "3") (pinfunction "D_3") (pintype "passive"))
    )
    (net (code "117") (name "Net-(T13-D)") (class "Default")
      (node (ref "R16") (pin "2") (pinfunction "2_2") (pintype "passive"))
      (node (ref "SW1") (pin "2") (pinfunction "2_2") (pintype "passive"))
      (node (ref "T13") (pin "3") (pinfunction "D_3") (pintype "passive"))
    )
    (net (code "118") (name "Net-(T14-D)") (class "Default")
      (node (ref "R13") (pin "2") (pinfunction "2_2") (pintype "passive"))
      (node (ref "SW1") (pin "1") (pinfunction "1_1") (pintype "passive"))
      (node (ref "T14") (pin "3") (pinfunction "D_3") (pintype "passive"))
    )
    (net (code "119") (name "P3V3") (class "Default")
      (node (ref "C45") (pin "2") (pinfunction "2_2") (pintype "passive"))
      (node (ref "C46") (pin "2") (pinfunction "2_2") (pintype "passive"))
      (node (ref "C47") (pin "2") (pinfunction "2_2") (pintype "passive"))
      (node (ref "IC1") (pin "4") (pinfunction "VCC_4") (pintype "power_in"))
      (node (ref "IC2") (pin "18") (pinfunction "A0_18") (pintype "bidirectional"))
      (node (ref "IC2") (pin "21") (pinfunction "VCC_21") (pintype "power_in"))
      (node (ref "IC2") (pin "24") (pinfunction "~{RESET}_24") (pintype "input"))
      (node (ref "IC3") (pin "21") (pinfunction "VCC_21") (pintype "power_in"))
      (node (ref "IC3") (pin "24") (pinfunction "~{RESET}_24") (pintype "input"))
      (node (ref "IC4") (pin "21") (pinfunction "VCC_21") (pintype "power_in"))
      (node (ref "IC4") (pin "24") (pinfunction "~{RESET}_24") (pintype "input"))
      (node (ref "IC5") (pin "4") (pinfunction "VCC_4") (pintype "power_in"))
      (node (ref "R41") (pin "1") (pinfunction "1_1") (pintype "passive"))
      (node (ref "R49") (pin "1") (pinfunction "1_1") (pintype "passive"))
      (node (ref "R57") (pin "2") (pinfunction "2_2") (pintype "passive"))
      (node (ref "R58") (pin "2") (pinfunction "2_2") (pintype "passive"))
      (node (ref "T1") (pin "2") (pinfunction "S_2") (pintype "passive"))
      (node (ref "T2") (pin "2") (pinfunction "S_2") (pintype "passive"))
      (node (ref "T3") (pin "2") (pinfunction "S_2") (pintype "passive"))
      (node (ref "T4") (pin "2") (pinfunction "S_2") (pintype "passive"))
      (node (ref "TP10") (pin "1") (pinfunction "1_1") (pintype "bidirectional"))
    )
    (net (code "120") (name "P3V3_MP") (class "Default")
      (node (ref "J40") (pin "30") (pinfunction "30_30") (pintype "bidirectional"))
      (node (ref "R59") (pin "2") (pinfunction "2_2") (pintype "passive"))
      (node (ref "R60") (pin "2") (pinfunction "2_2") (pintype "passive"))
    )
    (net (code "121") (name "P6V0A") (class "Default")
      (node (ref "R29") (pin "1") (pinfunction "1_1") (pintype "passive"))
      (node (ref "R33") (pin "1") (pinfunction "1_1") (pintype "passive"))
      (node (ref "R55") (pin "2") (pinfunction "2_2") (pintype "passive"))
      (node (ref "TP8") (pin "1") (pinfunction "1_1") (pintype "bidirectional"))
    )
    (net (code "122") (name "P12V0A") (class "Default")
      (node (ref "J40") (pin "28") (pinfunction "28_28") (pintype "bidirectional"))
      (node (ref "J40") (pin "29") (pinfunction "29_29") (pintype "bidirectional"))
      (node (ref "R11") (pin "1") (pinfunction "1_1") (pintype "passive"))
      (node (ref "R14") (pin "1") (pinfunction "1_1") (pintype "passive"))
      (node (ref "R51") (pin "1") (pinfunction "1_1") (pintype "passive"))
      (node (ref "TP6") (pin "1") (pinfunction "1_1") (pintype "bidirectional"))
    )
    (net (code "123") (name "unconnected-(IC1-NC-Pad5)") (class "Default")
      (node (ref "IC1") (pin "5") (pinfunction "NC_5") (pintype "passive"))
    )
    (net (code "124") (name "unconnected-(IC2-P12-Pad12)") (class "Default")
      (node (ref "IC2") (pin "12") (pinfunction "P12_12") (pintype "bidirectional"))
    )
    (net (code "125") (name "unconnected-(IC2-P13-Pad13)") (class "Default")
      (node (ref "IC2") (pin "13") (pinfunction "P13_13") (pintype "bidirectional"))
    )
    (net (code "126") (name "unconnected-(IC2-P14-Pad14)") (class "Default")
      (node (ref "IC2") (pin "14") (pinfunction "P14_14") (pintype "bidirectional"))
    )
    (net (code "127") (name "unconnected-(IC2-P15-Pad15)") (class "Default")
      (node (ref "IC2") (pin "15") (pinfunction "P15_15") (pintype "bidirectional"))
    )
    (net (code "128") (name "unconnected-(IC2-P16-Pad16)") (class "Default")
      (node (ref "IC2") (pin "16") (pinfunction "P16_16") (pintype "bidirectional"))
    )
    (net (code "129") (name "unconnected-(IC2-P17-Pad17)") (class "Default")
      (node (ref "IC2") (pin "17") (pinfunction "P17_17") (pintype "bidirectional"))
    )
    (net (code "130") (name "unconnected-(IC2-~{INT}-Pad22)") (class "Default")
      (node (ref "IC2") (pin "22") (pinfunction "~{INT}_22") (pintype "output"))
    )
    (net (code "131") (name "unconnected-(IC3-~{INT}-Pad22)") (class "Default")
      (node (ref "IC3") (pin "22") (pinfunction "~{INT}_22") (pintype "output"))
    )
    (net (code "132") (name "unconnected-(IC4-~{INT}-Pad22)") (class "Default")
      (node (ref "IC4") (pin "22") (pinfunction "~{INT}_22") (pintype "output"))
    )
    (net (code "133") (name "unconnected-(IC5-NC-Pad5)") (class "Default")
      (node (ref "IC5") (pin "5") (pinfunction "NC_5") (pintype "passive"))
    )
    (net (code "134") (name "unconnected-(LD3-A-Pad2)") (class "Default")
      (node (ref "LD3") (pin "2") (pinfunction "A_2") (pintype "passive"))
    )
    (net (code "135") (name "unconnected-(LD5-A-Pad2)") (class "Default")
      (node (ref "LD5") (pin "2") (pinfunction "A_2") (pintype "passive"))
    )
  )
)
